# draft9.net
KiCad netlist of a schematic drawn in EAGLE
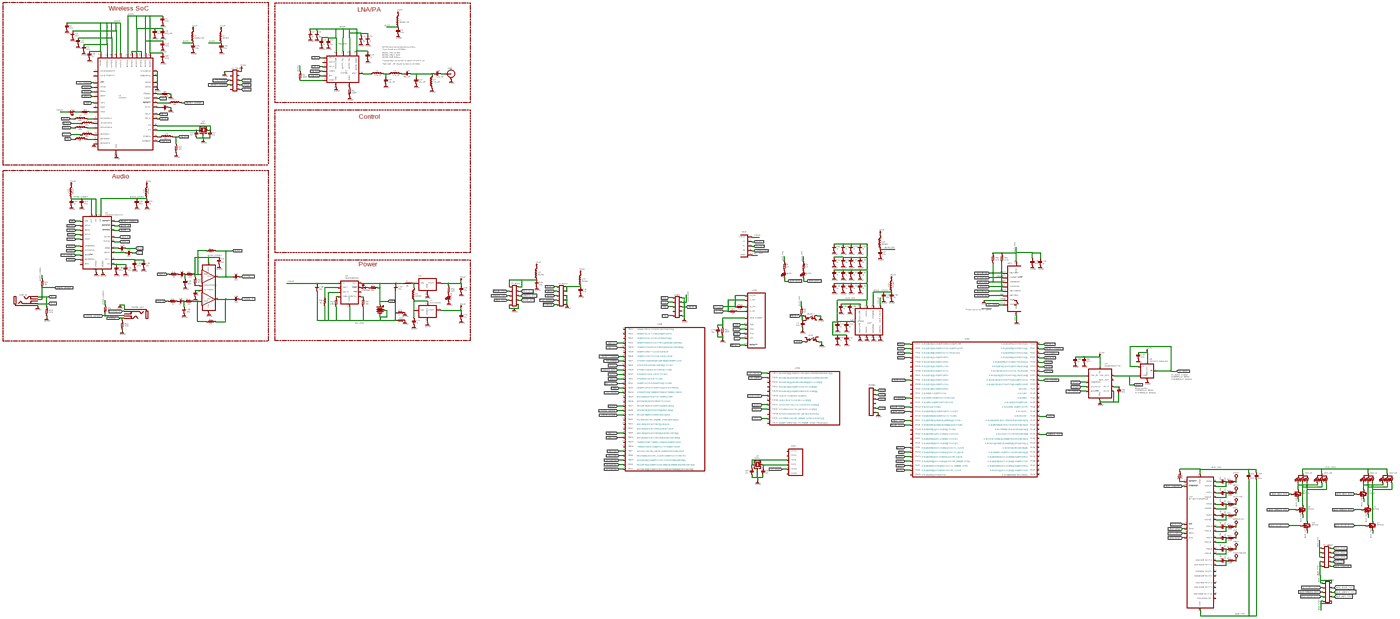
[diagram p0: schematic, sheet 1, overview]
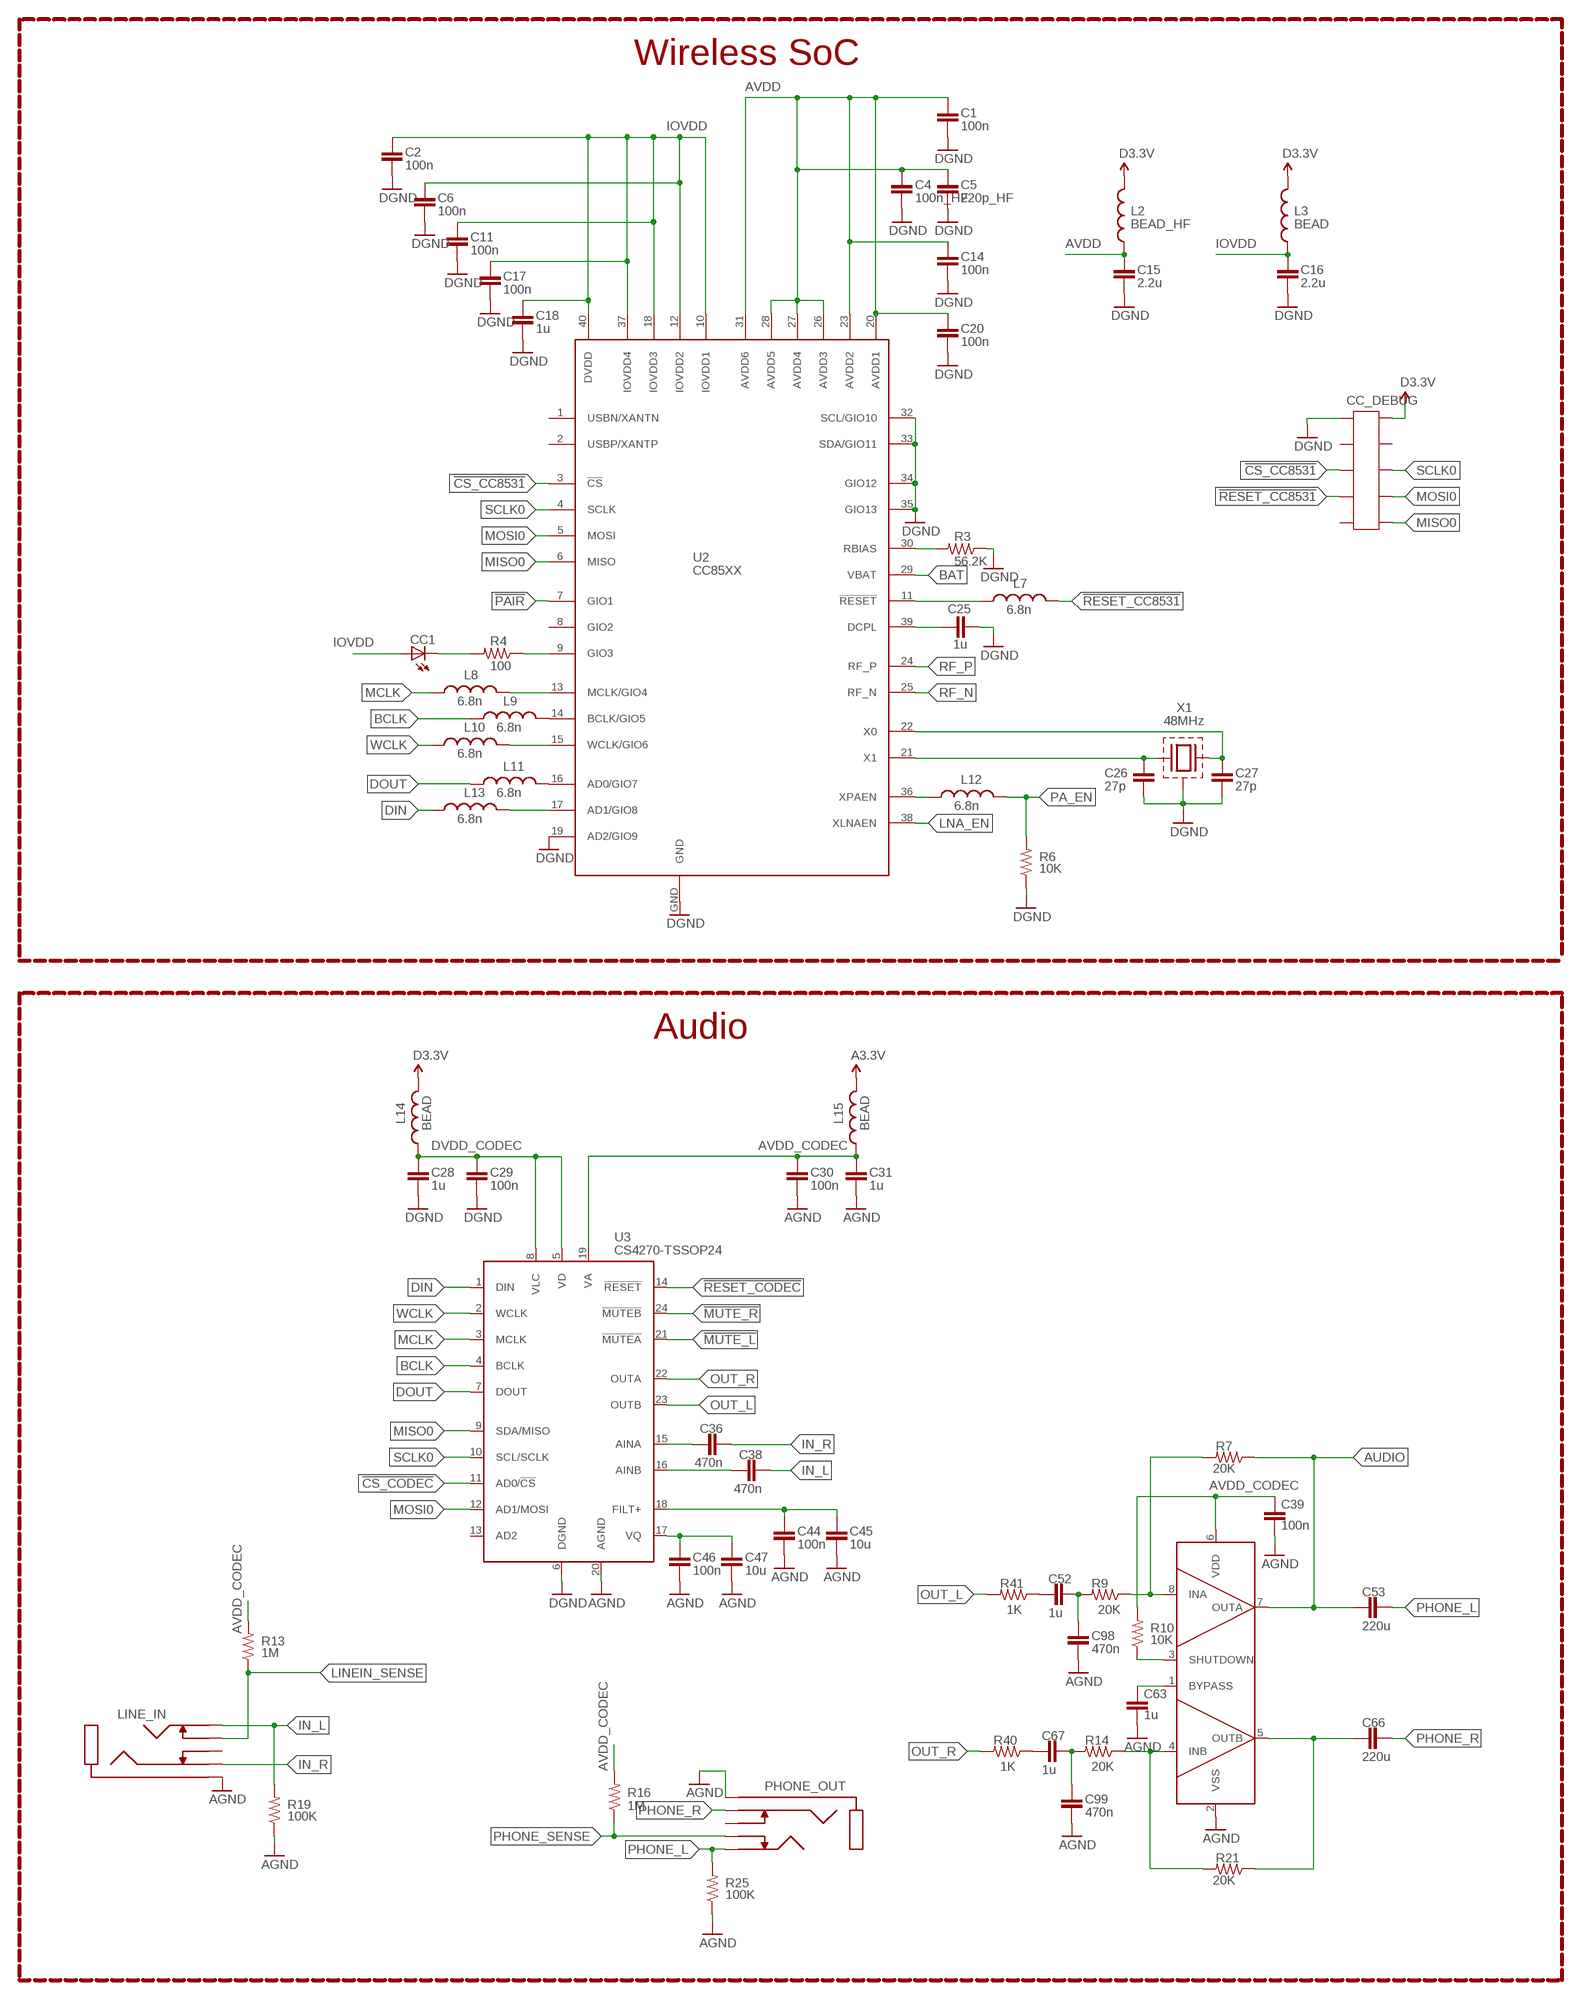
[diagram p1: schematic, sheet 1, part 1 of 4]
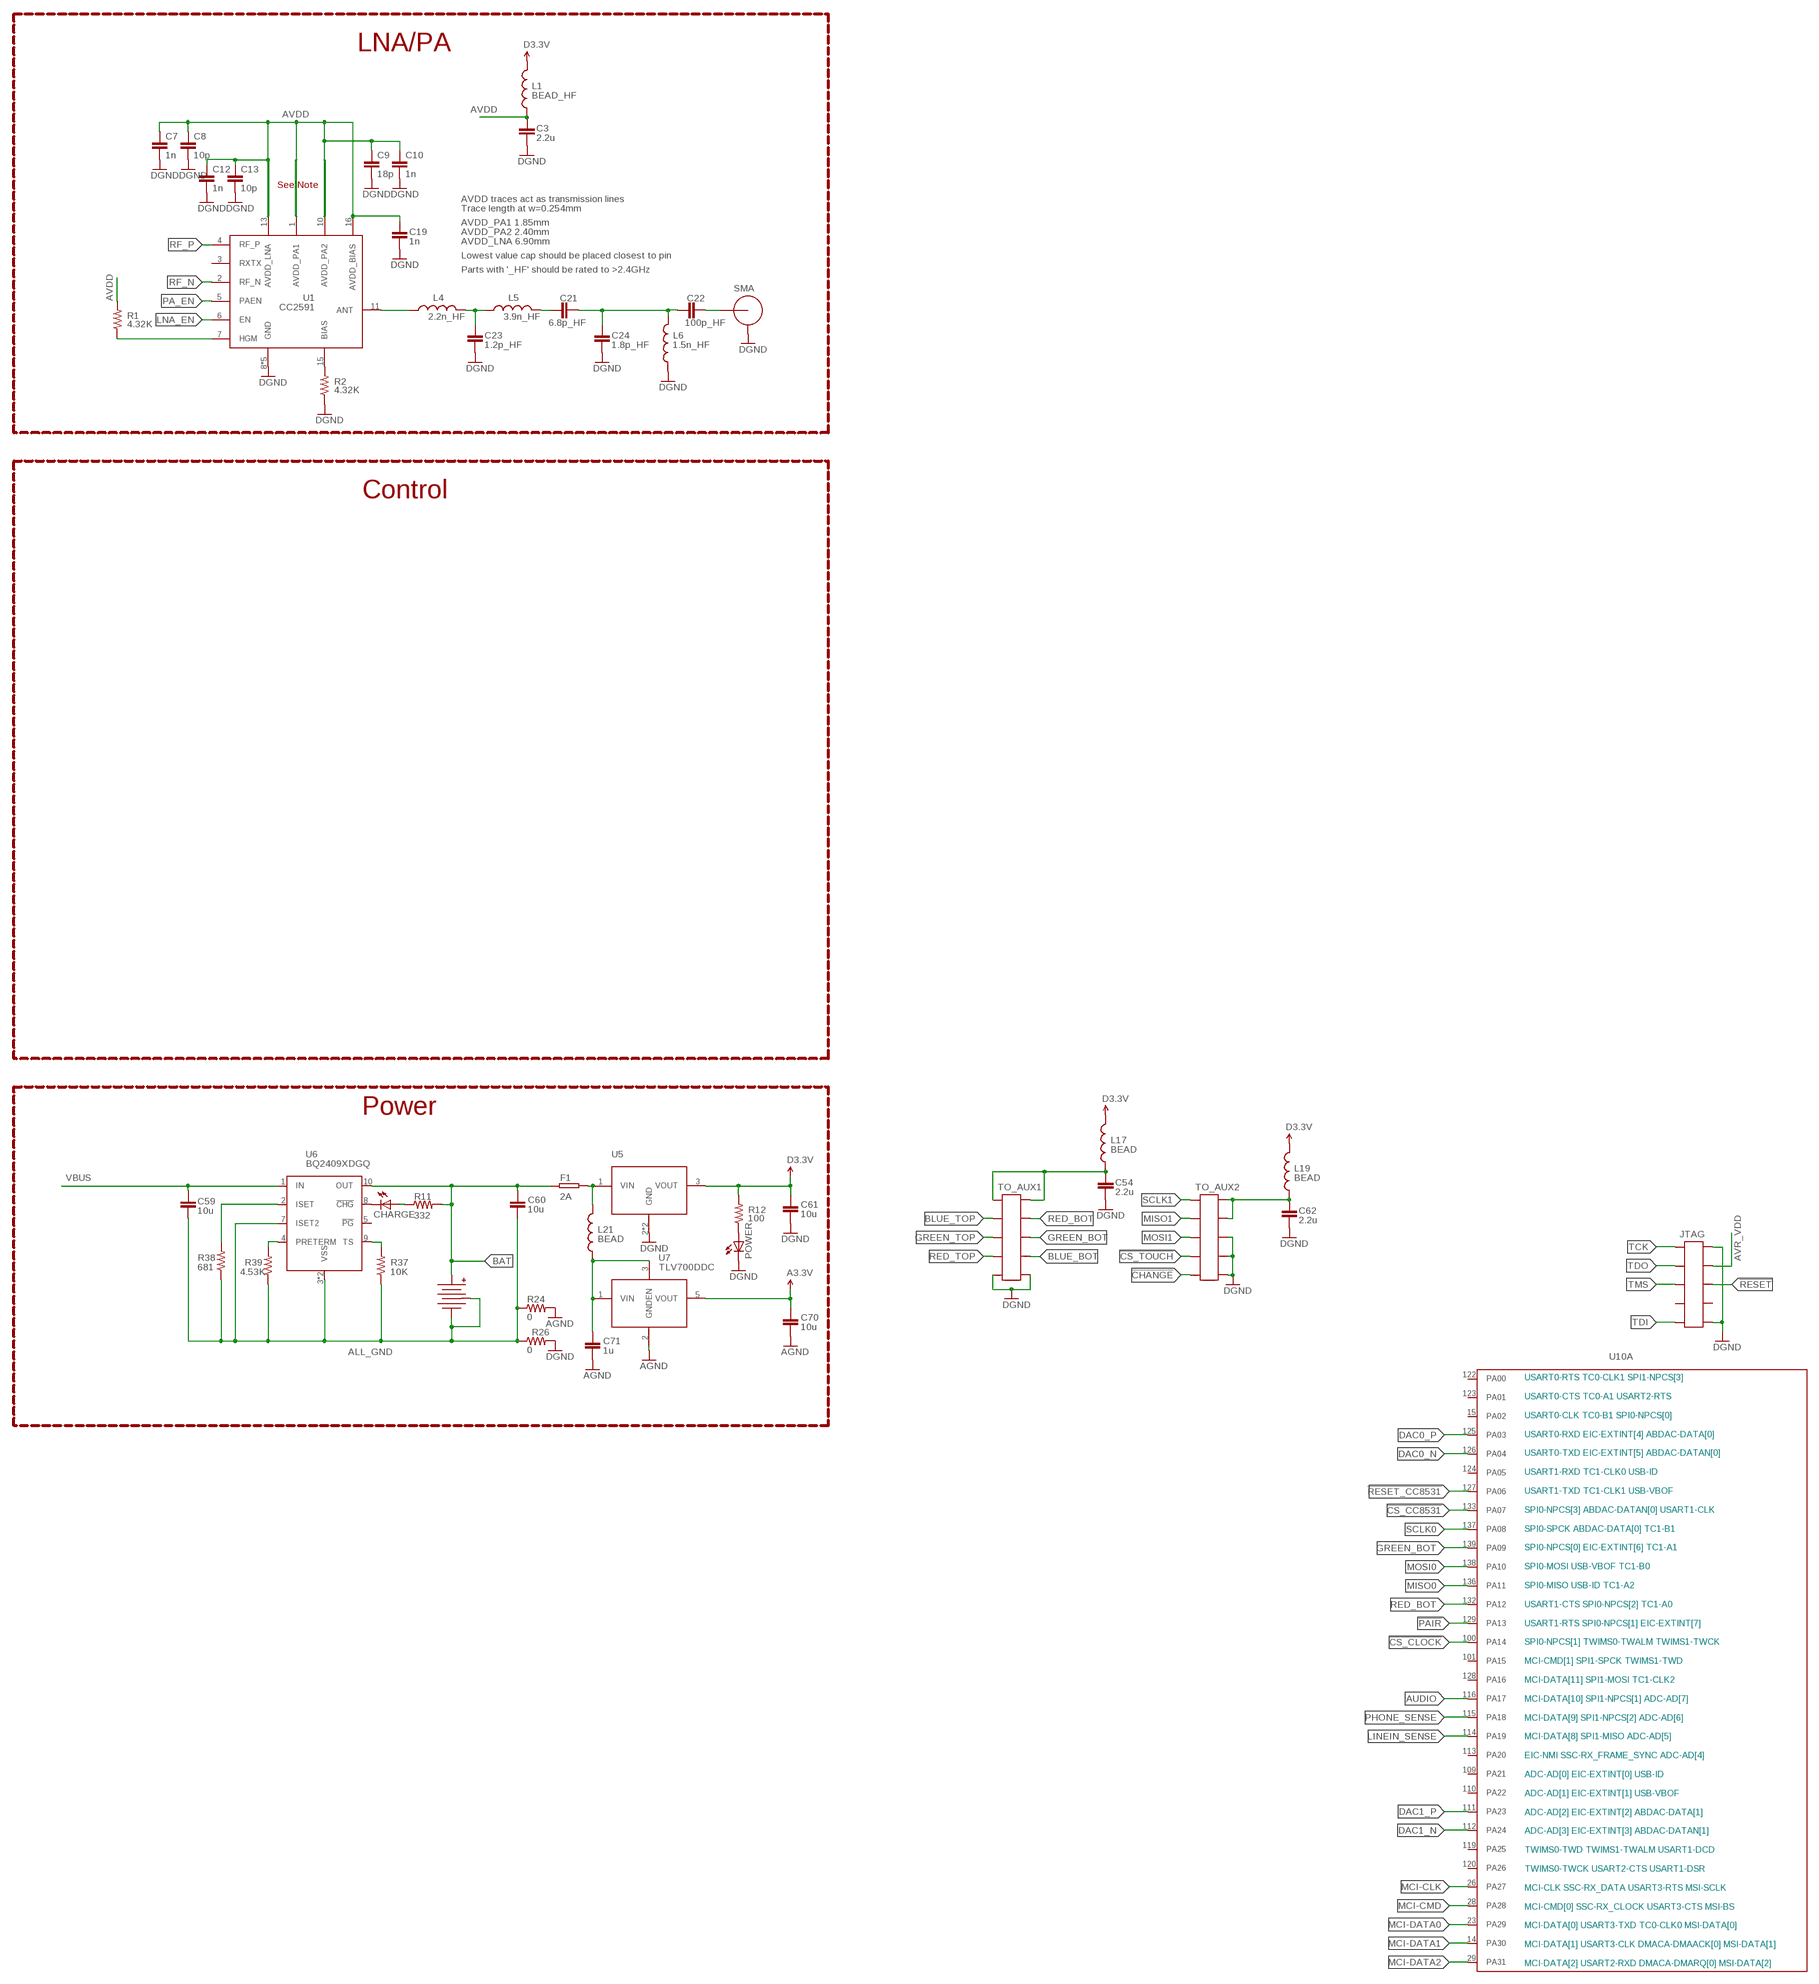
[diagram p2: schematic, sheet 1, part 2 of 4]
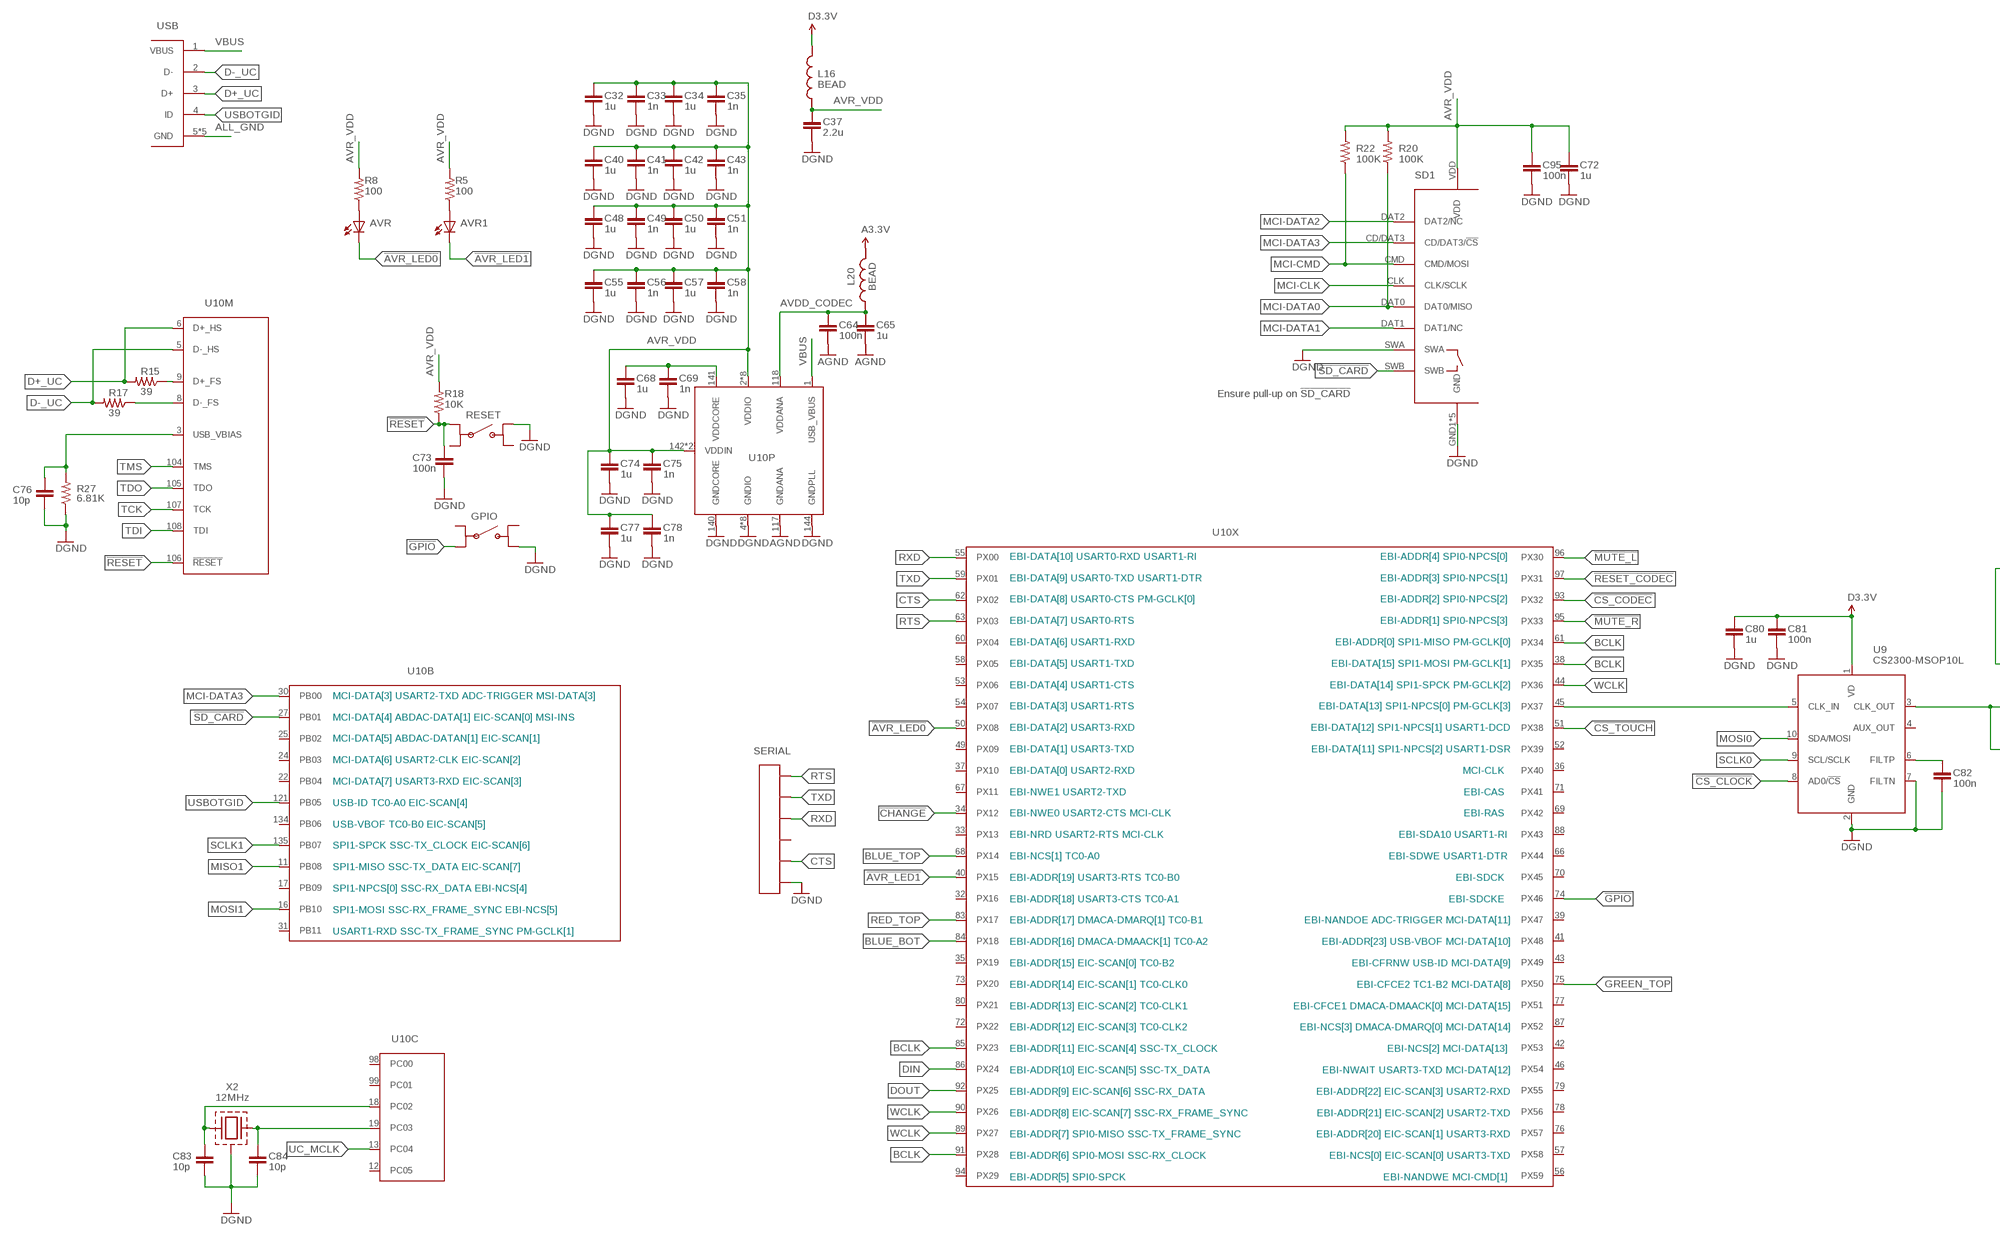
[diagram p3: schematic, sheet 1, part 3 of 4]
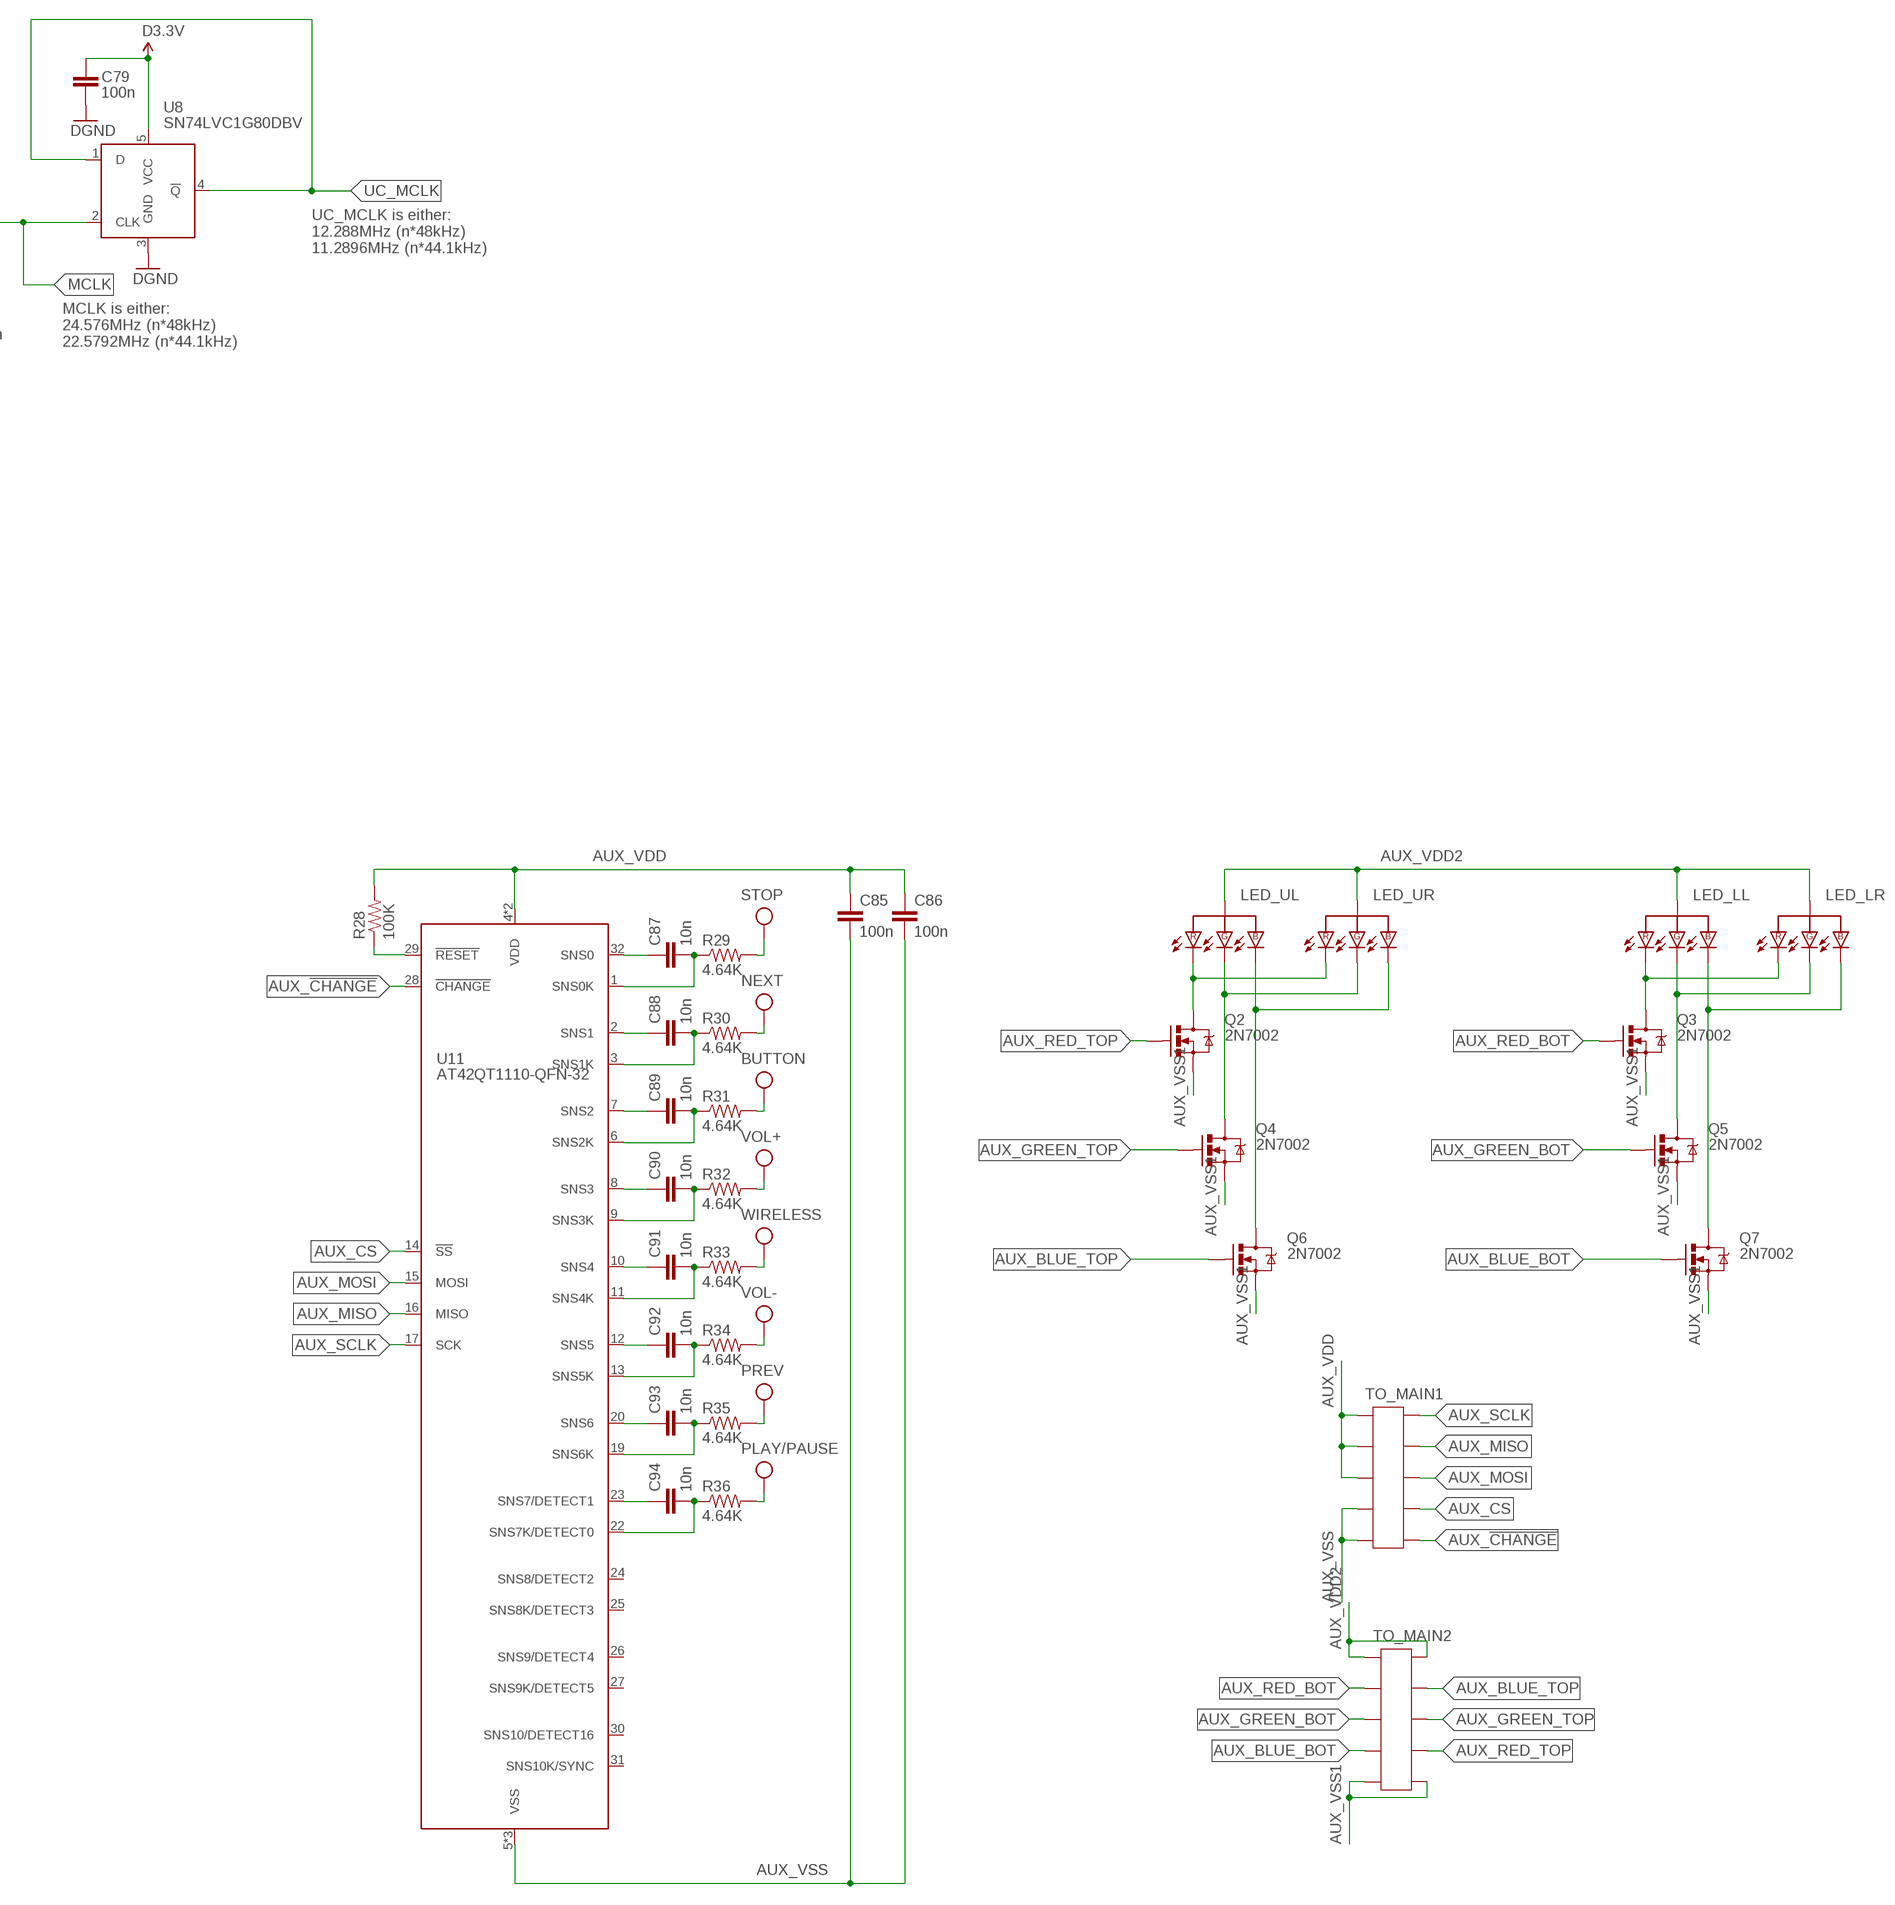
[diagram p4: schematic, sheet 1, part 4 of 4]

(export (version "E")
  (design (tool "Eeschema 10.0.6"))
  (components
    (comp (ref "AVR")
      (value "LED1206")
      (footprint "eagle-import:LED-1206")
      (libsource (lib "eagle-import") (part "LED1206"))
    )
    (comp (ref "AVR1")
      (value "LED1206")
      (footprint "eagle-import:LED-1206")
      (libsource (lib "eagle-import") (part "LED1206"))
    )
    (comp (ref "BATTERY")
      (value "BATTERY-LIPO-JST")
      (footprint "eagle-import:1775469-2")
      (libsource (lib "eagle-import") (part "BATTERY-LIPO-JST"))
    )
    (comp (ref "BUTTON")
      (value "TOUCH_PAD-CIRCLE-10MM")
      (footprint "eagle-import:TOUCH-CIRCLE-10MM")
      (libsource (lib "eagle-import") (part "TOUCH_PAD-CIRCLE-10MM"))
    )
    (comp (ref "C1")
      (value "100n")
      (footprint "eagle-import:C0603")
      (libsource (lib "eagle-import") (part "C-EUC0603"))
    )
    (comp (ref "C2")
      (value "100n")
      (footprint "eagle-import:C0603")
      (libsource (lib "eagle-import") (part "C-EUC0603"))
    )
    (comp (ref "C3")
      (value "2.2u")
      (footprint "eagle-import:C0603")
      (libsource (lib "eagle-import") (part "C-EUC0603"))
    )
    (comp (ref "C4")
      (value "100n_HF")
      (footprint "eagle-import:C0603")
      (libsource (lib "eagle-import") (part "C-EUC0603"))
    )
    (comp (ref "C5")
      (value "220p_HF")
      (footprint "eagle-import:C0603")
      (libsource (lib "eagle-import") (part "C-EUC0603"))
    )
    (comp (ref "C6")
      (value "100n")
      (footprint "eagle-import:C0603")
      (libsource (lib "eagle-import") (part "C-EUC0603"))
    )
    (comp (ref "C7")
      (value "1n")
      (footprint "eagle-import:C0603")
      (libsource (lib "eagle-import") (part "C-EUC0603"))
    )
    (comp (ref "C8")
      (value "10p")
      (footprint "eagle-import:C0603")
      (libsource (lib "eagle-import") (part "C-EUC0603"))
    )
    (comp (ref "C9")
      (value "18p")
      (footprint "eagle-import:C0603")
      (libsource (lib "eagle-import") (part "C-EUC0603"))
    )
    (comp (ref "C10")
      (value "1n")
      (footprint "eagle-import:C0603")
      (libsource (lib "eagle-import") (part "C-EUC0603"))
    )
    (comp (ref "C11")
      (value "100n")
      (footprint "eagle-import:C0603")
      (libsource (lib "eagle-import") (part "C-EUC0603"))
    )
    (comp (ref "C12")
      (value "1n")
      (footprint "eagle-import:C0603")
      (libsource (lib "eagle-import") (part "C-EUC0603"))
    )
    (comp (ref "C13")
      (value "10p")
      (footprint "eagle-import:C0603")
      (libsource (lib "eagle-import") (part "C-EUC0603"))
    )
    (comp (ref "C14")
      (value "100n")
      (footprint "eagle-import:C0603")
      (libsource (lib "eagle-import") (part "C-EUC0603"))
    )
    (comp (ref "C15")
      (value "2.2u")
      (footprint "eagle-import:C0603")
      (libsource (lib "eagle-import") (part "C-EUC0603"))
    )
    (comp (ref "C16")
      (value "2.2u")
      (footprint "eagle-import:C0603")
      (libsource (lib "eagle-import") (part "C-EUC0603"))
    )
    (comp (ref "C17")
      (value "100n")
      (footprint "eagle-import:C0603")
      (libsource (lib "eagle-import") (part "C-EUC0603"))
    )
    (comp (ref "C18")
      (value "1u")
      (footprint "eagle-import:C0603")
      (libsource (lib "eagle-import") (part "C-EUC0603"))
    )
    (comp (ref "C19")
      (value "1n")
      (footprint "eagle-import:C0603")
      (libsource (lib "eagle-import") (part "C-EUC0603"))
    )
    (comp (ref "C20")
      (value "100n")
      (footprint "eagle-import:C0603")
      (libsource (lib "eagle-import") (part "C-EUC0603"))
    )
    (comp (ref "C21")
      (value "6.8p_HF")
      (footprint "eagle-import:C0603")
      (libsource (lib "eagle-import") (part "C-EUC0603"))
    )
    (comp (ref "C22")
      (value "100p_HF")
      (footprint "eagle-import:C0603")
      (libsource (lib "eagle-import") (part "C-EUC0603"))
    )
    (comp (ref "C23")
      (value "1.2p_HF")
      (footprint "eagle-import:C0603")
      (libsource (lib "eagle-import") (part "C-EUC0603"))
    )
    (comp (ref "C24")
      (value "1.8p_HF")
      (footprint "eagle-import:C0603")
      (libsource (lib "eagle-import") (part "C-EUC0603"))
    )
    (comp (ref "C25")
      (value "1u")
      (footprint "eagle-import:C0603")
      (libsource (lib "eagle-import") (part "C-EUC0603"))
    )
    (comp (ref "C26")
      (value "27p")
      (footprint "eagle-import:C0603")
      (libsource (lib "eagle-import") (part "C-EUC0603"))
    )
    (comp (ref "C27")
      (value "27p")
      (footprint "eagle-import:C0603")
      (libsource (lib "eagle-import") (part "C-EUC0603"))
    )
    (comp (ref "C28")
      (value "1u")
      (footprint "eagle-import:C0603")
      (libsource (lib "eagle-import") (part "C-EUC0603"))
    )
    (comp (ref "C29")
      (value "100n")
      (footprint "eagle-import:C0603")
      (libsource (lib "eagle-import") (part "C-EUC0603"))
    )
    (comp (ref "C30")
      (value "100n")
      (footprint "eagle-import:C0603")
      (libsource (lib "eagle-import") (part "C-EUC0603"))
    )
    (comp (ref "C31")
      (value "1u")
      (footprint "eagle-import:C0603")
      (libsource (lib "eagle-import") (part "C-EUC0603"))
    )
    (comp (ref "C32")
      (value "1u")
      (footprint "eagle-import:C0603")
      (libsource (lib "eagle-import") (part "C-EUC0603"))
    )
    (comp (ref "C33")
      (value "1n")
      (footprint "eagle-import:C0603")
      (libsource (lib "eagle-import") (part "C-EUC0603"))
    )
    (comp (ref "C34")
      (value "1u")
      (footprint "eagle-import:C0603")
      (libsource (lib "eagle-import") (part "C-EUC0603"))
    )
    (comp (ref "C35")
      (value "1n")
      (footprint "eagle-import:C0603")
      (libsource (lib "eagle-import") (part "C-EUC0603"))
    )
    (comp (ref "C36")
      (value "470n")
      (footprint "eagle-import:C0603")
      (libsource (lib "eagle-import") (part "C-EUC0603"))
    )
    (comp (ref "C37")
      (value "2.2u")
      (footprint "eagle-import:C0603@1")
      (libsource (lib "eagle-import") (part "rcl_C-EUC0603"))
    )
    (comp (ref "C38")
      (value "470n")
      (footprint "eagle-import:C0603")
      (libsource (lib "eagle-import") (part "C-EUC0603"))
    )
    (comp (ref "C39")
      (value "100n")
      (footprint "eagle-import:C0603")
      (libsource (lib "eagle-import") (part "C-EUC0603"))
    )
    (comp (ref "C40")
      (value "1u")
      (footprint "eagle-import:C0603")
      (libsource (lib "eagle-import") (part "C-EUC0603"))
    )
    (comp (ref "C41")
      (value "1n")
      (footprint "eagle-import:C0603")
      (libsource (lib "eagle-import") (part "C-EUC0603"))
    )
    (comp (ref "C42")
      (value "1u")
      (footprint "eagle-import:C0603")
      (libsource (lib "eagle-import") (part "C-EUC0603"))
    )
    (comp (ref "C43")
      (value "1n")
      (footprint "eagle-import:C0603")
      (libsource (lib "eagle-import") (part "C-EUC0603"))
    )
    (comp (ref "C44")
      (value "100n")
      (footprint "eagle-import:C0603")
      (libsource (lib "eagle-import") (part "C-EUC0603"))
    )
    (comp (ref "C45")
      (value "10u")
      (footprint "eagle-import:C0603")
      (libsource (lib "eagle-import") (part "C-EUC0603"))
    )
    (comp (ref "C46")
      (value "100n")
      (footprint "eagle-import:C0603")
      (libsource (lib "eagle-import") (part "C-EUC0603"))
    )
    (comp (ref "C47")
      (value "10u")
      (footprint "eagle-import:C0603")
      (libsource (lib "eagle-import") (part "C-EUC0603"))
    )
    (comp (ref "C48")
      (value "1u")
      (footprint "eagle-import:C0603")
      (libsource (lib "eagle-import") (part "C-EUC0603"))
    )
    (comp (ref "C49")
      (value "1n")
      (footprint "eagle-import:C0603")
      (libsource (lib "eagle-import") (part "C-EUC0603"))
    )
    (comp (ref "C50")
      (value "1u")
      (footprint "eagle-import:C0603")
      (libsource (lib "eagle-import") (part "C-EUC0603"))
    )
    (comp (ref "C51")
      (value "1n")
      (footprint "eagle-import:C0603")
      (libsource (lib "eagle-import") (part "C-EUC0603"))
    )
    (comp (ref "C52")
      (value "1u")
      (footprint "eagle-import:C0603")
      (libsource (lib "eagle-import") (part "C-EUC0603"))
    )
    (comp (ref "C53")
      (value "220u")
      (footprint "eagle-import:C1210")
      (libsource (lib "eagle-import") (part "C-EUC1210"))
    )
    (comp (ref "C54")
      (value "2.2u")
      (footprint "eagle-import:C0603")
      (libsource (lib "eagle-import") (part "C-EUC0603"))
    )
    (comp (ref "C55")
      (value "1u")
      (footprint "eagle-import:C0603")
      (libsource (lib "eagle-import") (part "C-EUC0603"))
    )
    (comp (ref "C56")
      (value "1n")
      (footprint "eagle-import:C0603")
      (libsource (lib "eagle-import") (part "C-EUC0603"))
    )
    (comp (ref "C57")
      (value "1u")
      (footprint "eagle-import:C0603")
      (libsource (lib "eagle-import") (part "C-EUC0603"))
    )
    (comp (ref "C58")
      (value "1n")
      (footprint "eagle-import:C0603")
      (libsource (lib "eagle-import") (part "C-EUC0603"))
    )
    (comp (ref "C59")
      (value "10u")
      (footprint "eagle-import:C0603")
      (libsource (lib "eagle-import") (part "C-EUC0603"))
    )
    (comp (ref "C60")
      (value "10u")
      (footprint "eagle-import:C0603")
      (libsource (lib "eagle-import") (part "C-EUC0603"))
    )
    (comp (ref "C61")
      (value "10u")
      (footprint "eagle-import:C0603")
      (libsource (lib "eagle-import") (part "C-EUC0603"))
    )
    (comp (ref "C62")
      (value "2.2u")
      (footprint "eagle-import:C0603")
      (libsource (lib "eagle-import") (part "C-EUC0603"))
    )
    (comp (ref "C63")
      (value "1u")
      (footprint "eagle-import:C0603")
      (libsource (lib "eagle-import") (part "C-EUC0603"))
    )
    (comp (ref "C64")
      (value "100n")
      (footprint "eagle-import:C0603")
      (libsource (lib "eagle-import") (part "C-EUC0603"))
    )
    (comp (ref "C65")
      (value "1u")
      (footprint "eagle-import:C0603")
      (libsource (lib "eagle-import") (part "C-EUC0603"))
    )
    (comp (ref "C66")
      (value "220u")
      (footprint "eagle-import:C1210")
      (libsource (lib "eagle-import") (part "C-EUC1210"))
    )
    (comp (ref "C67")
      (value "1u")
      (footprint "eagle-import:C0603")
      (libsource (lib "eagle-import") (part "C-EUC0603"))
    )
    (comp (ref "C68")
      (value "1u")
      (footprint "eagle-import:C0603")
      (libsource (lib "eagle-import") (part "C-EUC0603"))
    )
    (comp (ref "C69")
      (value "1n")
      (footprint "eagle-import:C0603")
      (libsource (lib "eagle-import") (part "C-EUC0603"))
    )
    (comp (ref "C70")
      (value "10u")
      (footprint "eagle-import:C0603@1")
      (libsource (lib "eagle-import") (part "rcl_C-EUC0603"))
    )
    (comp (ref "C71")
      (value "1u")
      (footprint "eagle-import:C0603")
      (libsource (lib "eagle-import") (part "C-EUC0603"))
    )
    (comp (ref "C72")
      (value "1u")
      (footprint "eagle-import:C0603")
      (libsource (lib "eagle-import") (part "C-EUC0603"))
    )
    (comp (ref "C73")
      (value "100n")
      (footprint "eagle-import:C0603")
      (libsource (lib "eagle-import") (part "C-EUC0603"))
    )
    (comp (ref "C74")
      (value "1u")
      (footprint "eagle-import:C0603")
      (libsource (lib "eagle-import") (part "C-EUC0603"))
    )
    (comp (ref "C75")
      (value "1n")
      (footprint "eagle-import:C0603")
      (libsource (lib "eagle-import") (part "C-EUC0603"))
    )
    (comp (ref "C76")
      (value "10p")
      (footprint "eagle-import:C0603")
      (libsource (lib "eagle-import") (part "C-EUC0603"))
    )
    (comp (ref "C77")
      (value "1u")
      (footprint "eagle-import:C0603")
      (libsource (lib "eagle-import") (part "C-EUC0603"))
    )
    (comp (ref "C78")
      (value "1n")
      (footprint "eagle-import:C0603")
      (libsource (lib "eagle-import") (part "C-EUC0603"))
    )
    (comp (ref "C79")
      (value "100n")
      (footprint "eagle-import:C0603")
      (libsource (lib "eagle-import") (part "C-EUC0603"))
    )
    (comp (ref "C80")
      (value "1u")
      (footprint "eagle-import:C0603")
      (libsource (lib "eagle-import") (part "C-EUC0603"))
    )
    (comp (ref "C81")
      (value "100n")
      (footprint "eagle-import:C0603")
      (libsource (lib "eagle-import") (part "C-EUC0603"))
    )
    (comp (ref "C82")
      (value "100n")
      (footprint "eagle-import:C0603")
      (libsource (lib "eagle-import") (part "C-EUC0603"))
    )
    (comp (ref "C83")
      (value "10p")
      (footprint "eagle-import:C0603")
      (libsource (lib "eagle-import") (part "C-EUC0603"))
    )
    (comp (ref "C84")
      (value "10p")
      (footprint "eagle-import:C0603")
      (libsource (lib "eagle-import") (part "C-EUC0603"))
    )
    (comp (ref "C85")
      (value "100n")
      (footprint "eagle-import:C0603")
      (libsource (lib "eagle-import") (part "C-EUC0603"))
    )
    (comp (ref "C86")
      (value "100n")
      (footprint "eagle-import:C0603")
      (libsource (lib "eagle-import") (part "C-EUC0603"))
    )
    (comp (ref "C87")
      (value "10n")
      (footprint "eagle-import:C0603")
      (libsource (lib "eagle-import") (part "C-EUC0603"))
    )
    (comp (ref "C88")
      (value "10n")
      (footprint "eagle-import:C0603")
      (libsource (lib "eagle-import") (part "C-EUC0603"))
    )
    (comp (ref "C89")
      (value "10n")
      (footprint "eagle-import:C0603")
      (libsource (lib "eagle-import") (part "C-EUC0603"))
    )
    (comp (ref "C90")
      (value "10n")
      (footprint "eagle-import:C0603")
      (libsource (lib "eagle-import") (part "C-EUC0603"))
    )
    (comp (ref "C91")
      (value "10n")
      (footprint "eagle-import:C0603")
      (libsource (lib "eagle-import") (part "C-EUC0603"))
    )
    (comp (ref "C92")
      (value "10n")
      (footprint "eagle-import:C0603")
      (libsource (lib "eagle-import") (part "C-EUC0603"))
    )
    (comp (ref "C93")
      (value "10n")
      (footprint "eagle-import:C0603")
      (libsource (lib "eagle-import") (part "C-EUC0603"))
    )
    (comp (ref "C94")
      (value "10n")
      (footprint "eagle-import:C0603")
      (libsource (lib "eagle-import") (part "C-EUC0603"))
    )
    (comp (ref "C95")
      (value "100n")
      (footprint "eagle-import:C0603")
      (libsource (lib "eagle-import") (part "C-EUC0603"))
    )
    (comp (ref "C98")
      (value "470n")
      (footprint "eagle-import:C0603")
      (libsource (lib "eagle-import") (part "C-EUC0603"))
    )
    (comp (ref "C99")
      (value "470n")
      (footprint "eagle-import:C0603")
      (libsource (lib "eagle-import") (part "C-EUC0603"))
    )
    (comp (ref "CC1")
      (value "LED1206")
      (footprint "eagle-import:LED-1206")
      (libsource (lib "eagle-import") (part "LED1206"))
    )
    (comp (ref "CC_DEBUG")
      (value "HEADER-10P-SMD-MALE2")
      (footprint "eagle-import:HEADER-10P-1.27MM")
      (libsource (lib "eagle-import") (part "HEADER-10P-SMD-MALE2"))
    )
    (comp (ref "CHARGE")
      (value "LED1206")
      (footprint "eagle-import:LED-1206")
      (libsource (lib "eagle-import") (part "LED1206"))
    )
    (comp (ref "F1")
      (value "2A")
      (footprint "eagle-import:1210")
      (libsource (lib "eagle-import") (part "PTC_FUSE"))
    )
    (comp (ref "GPIO")
      (value "TACT_SWITCH-PTS-525")
      (footprint "eagle-import:PTS-525")
      (libsource (lib "eagle-import") (part "TACT_SWITCH-PTS-525"))
    )
    (comp (ref "JTAG")
      (value "HEADER-10P-SMD-MALE2")
      (footprint "eagle-import:HEADER-10P-1.27MM")
      (libsource (lib "eagle-import") (part "HEADER-10P-SMD-MALE2"))
    )
    (comp (ref "L1")
      (value "BEAD_HF")
      (footprint "eagle-import:0603")
      (libsource (lib "eagle-import") (part "INDUCTOR0603"))
    )
    (comp (ref "L2")
      (value "BEAD_HF")
      (footprint "eagle-import:0603")
      (libsource (lib "eagle-import") (part "INDUCTOR0603"))
    )
    (comp (ref "L3")
      (value "BEAD")
      (footprint "eagle-import:0603")
      (libsource (lib "eagle-import") (part "INDUCTOR0603"))
    )
    (comp (ref "L4")
      (value "2.2n_HF")
      (footprint "eagle-import:0603")
      (libsource (lib "eagle-import") (part "INDUCTOR0603"))
    )
    (comp (ref "L5")
      (value "3.9n_HF")
      (footprint "eagle-import:0603")
      (libsource (lib "eagle-import") (part "INDUCTOR0603"))
    )
    (comp (ref "L6")
      (value "1.5n_HF")
      (footprint "eagle-import:0603")
      (libsource (lib "eagle-import") (part "INDUCTOR0603"))
    )
    (comp (ref "L7")
      (value "6.8n")
      (footprint "eagle-import:0603")
      (libsource (lib "eagle-import") (part "INDUCTOR0603"))
    )
    (comp (ref "L8")
      (value "6.8n")
      (footprint "eagle-import:0603")
      (libsource (lib "eagle-import") (part "INDUCTOR0603"))
    )
    (comp (ref "L9")
      (value "6.8n")
      (footprint "eagle-import:0603")
      (libsource (lib "eagle-import") (part "INDUCTOR0603"))
    )
    (comp (ref "L10")
      (value "6.8n")
      (footprint "eagle-import:0603")
      (libsource (lib "eagle-import") (part "INDUCTOR0603"))
    )
    (comp (ref "L11")
      (value "6.8n")
      (footprint "eagle-import:0603")
      (libsource (lib "eagle-import") (part "INDUCTOR0603"))
    )
    (comp (ref "L12")
      (value "6.8n")
      (footprint "eagle-import:0603@1")
      (libsource (lib "eagle-import") (part "SparkFun-Passives_INDUCTOR0603"))
    )
    (comp (ref "L13")
      (value "6.8n")
      (footprint "eagle-import:0603")
      (libsource (lib "eagle-import") (part "INDUCTOR0603"))
    )
    (comp (ref "L14")
      (value "BEAD")
      (footprint "eagle-import:0603")
      (libsource (lib "eagle-import") (part "INDUCTOR0603"))
    )
    (comp (ref "L15")
      (value "BEAD")
      (footprint "eagle-import:0603@1")
      (libsource (lib "eagle-import") (part "SparkFun-Passives_INDUCTOR0603"))
    )
    (comp (ref "L16")
      (value "BEAD")
      (footprint "eagle-import:0603@1")
      (libsource (lib "eagle-import") (part "SparkFun-Passives_INDUCTOR0603"))
    )
    (comp (ref "L17")
      (value "BEAD")
      (footprint "eagle-import:0603")
      (libsource (lib "eagle-import") (part "INDUCTOR0603"))
    )
    (comp (ref "L19")
      (value "BEAD")
      (footprint "eagle-import:0603")
      (libsource (lib "eagle-import") (part "INDUCTOR0603"))
    )
    (comp (ref "L20")
      (value "BEAD")
      (footprint "eagle-import:0603")
      (libsource (lib "eagle-import") (part "INDUCTOR0603"))
    )
    (comp (ref "L21")
      (value "BEAD")
      (footprint "eagle-import:0603")
      (libsource (lib "eagle-import") (part "INDUCTOR0603"))
    )
    (comp (ref "LED_LL")
      (value "LED_RGB")
      (footprint "eagle-import:PLCC-4")
      (libsource (lib "eagle-import") (part "LED_RGB"))
    )
    (comp (ref "LED_LR")
      (value "LED_RGB")
      (footprint "eagle-import:PLCC-4")
      (libsource (lib "eagle-import") (part "LED_RGB"))
    )
    (comp (ref "LED_UL")
      (value "LED_RGB")
      (footprint "eagle-import:PLCC-4")
      (libsource (lib "eagle-import") (part "LED_RGB"))
    )
    (comp (ref "LED_UR")
      (value "LED_RGB")
      (footprint "eagle-import:PLCC-4")
      (libsource (lib "eagle-import") (part "LED_RGB"))
    )
    (comp (ref "LINE_IN")
      (value "PHONE_SW-STX-35332-5N")
      (footprint "eagle-import:STX-35332-5N")
      (libsource (lib "eagle-import") (part "PHONE_SW-STX-35332-5N"))
    )
    (comp (ref "NEXT")
      (value "TOUCH_PAD-CIRCLE-10MM")
      (footprint "eagle-import:TOUCH-CIRCLE-10MM")
      (libsource (lib "eagle-import") (part "TOUCH_PAD-CIRCLE-10MM"))
    )
    (comp (ref "PHONE_OUT")
      (value "PHONE_SW-STX-35332-5N")
      (footprint "eagle-import:STX-35332-5N")
      (libsource (lib "eagle-import") (part "PHONE_SW-STX-35332-5N"))
    )
    (comp (ref "PLAY/PAUSE")
      (value "TOUCH_PAD-CIRCLE-10MM")
      (footprint "eagle-import:TOUCH-CIRCLE-10MM")
      (libsource (lib "eagle-import") (part "TOUCH_PAD-CIRCLE-10MM"))
    )
    (comp (ref "POWER")
      (value "LED1206")
      (footprint "eagle-import:LED-1206")
      (libsource (lib "eagle-import") (part "LED1206"))
    )
    (comp (ref "PREV")
      (value "TOUCH_PAD-CIRCLE-10MM")
      (footprint "eagle-import:TOUCH-CIRCLE-10MM")
      (libsource (lib "eagle-import") (part "TOUCH_PAD-CIRCLE-10MM"))
    )
    (comp (ref "Q2")
      (value "2N7002")
      (footprint "eagle-import:SOT23-3")
      (libsource (lib "eagle-import") (part "MOSFET-NCHANNELSMD"))
    )
    (comp (ref "Q3")
      (value "2N7002")
      (footprint "eagle-import:SOT23-3")
      (libsource (lib "eagle-import") (part "MOSFET-NCHANNELSMD"))
    )
    (comp (ref "Q4")
      (value "2N7002")
      (footprint "eagle-import:SOT23-3")
      (libsource (lib "eagle-import") (part "MOSFET-NCHANNELSMD"))
    )
    (comp (ref "Q5")
      (value "2N7002")
      (footprint "eagle-import:SOT23-3")
      (libsource (lib "eagle-import") (part "MOSFET-NCHANNELSMD"))
    )
    (comp (ref "Q6")
      (value "2N7002")
      (footprint "eagle-import:SOT23-3")
      (libsource (lib "eagle-import") (part "MOSFET-NCHANNELSMD"))
    )
    (comp (ref "Q7")
      (value "2N7002")
      (footprint "eagle-import:SOT23-3")
      (libsource (lib "eagle-import") (part "MOSFET-NCHANNELSMD"))
    )
    (comp (ref "R1")
      (value "4.32K")
      (footprint "eagle-import:R0603")
      (libsource (lib "eagle-import") (part "R-US_R0603"))
    )
    (comp (ref "R2")
      (value "4.32K")
      (footprint "eagle-import:R0603")
      (libsource (lib "eagle-import") (part "R-US_R0603"))
    )
    (comp (ref "R3")
      (value "56.2K")
      (footprint "eagle-import:R0603")
      (libsource (lib "eagle-import") (part "R-US_R0603"))
    )
    (comp (ref "R4")
      (value "100")
      (footprint "eagle-import:R0603")
      (libsource (lib "eagle-import") (part "R-US_R0603"))
    )
    (comp (ref "R5")
      (value "100")
      (footprint "eagle-import:R0603")
      (libsource (lib "eagle-import") (part "R-US_R0603"))
    )
    (comp (ref "R6")
      (value "10K")
      (footprint "eagle-import:R0603")
      (libsource (lib "eagle-import") (part "R-US_R0603"))
    )
    (comp (ref "R7")
      (value "20K")
      (footprint "eagle-import:R0603")
      (libsource (lib "eagle-import") (part "R-US_R0603"))
    )
    (comp (ref "R8")
      (value "100")
      (footprint "eagle-import:R0603")
      (libsource (lib "eagle-import") (part "R-US_R0603"))
    )
    (comp (ref "R9")
      (value "20K")
      (footprint "eagle-import:R0603")
      (libsource (lib "eagle-import") (part "R-US_R0603"))
    )
    (comp (ref "R10")
      (value "10K")
      (footprint "eagle-import:R0603@1")
      (libsource (lib "eagle-import") (part "rcl_R-US_R0603"))
    )
    (comp (ref "R11")
      (value "332")
      (footprint "eagle-import:R0603")
      (libsource (lib "eagle-import") (part "R-US_R0603"))
    )
    (comp (ref "R12")
      (value "100")
      (footprint "eagle-import:R0603")
      (libsource (lib "eagle-import") (part "R-US_R0603"))
    )
    (comp (ref "R13")
      (value "1M")
      (footprint "eagle-import:R0603")
      (libsource (lib "eagle-import") (part "R-US_R0603"))
    )
    (comp (ref "R14")
      (value "20K")
      (footprint "eagle-import:R0603")
      (libsource (lib "eagle-import") (part "R-US_R0603"))
    )
    (comp (ref "R15")
      (value "39")
      (footprint "eagle-import:R0603")
      (libsource (lib "eagle-import") (part "R-US_R0603"))
    )
    (comp (ref "R16")
      (value "1M")
      (footprint "eagle-import:R0603")
      (libsource (lib "eagle-import") (part "R-US_R0603"))
    )
    (comp (ref "R17")
      (value "39")
      (footprint "eagle-import:R0603")
      (libsource (lib "eagle-import") (part "R-US_R0603"))
    )
    (comp (ref "R18")
      (value "10K")
      (footprint "eagle-import:R0603")
      (libsource (lib "eagle-import") (part "R-US_R0603"))
    )
    (comp (ref "R19")
      (value "100K")
      (footprint "eagle-import:R0603")
      (libsource (lib "eagle-import") (part "R-US_R0603"))
    )
    (comp (ref "R20")
      (value "100K")
      (footprint "eagle-import:R0603")
      (libsource (lib "eagle-import") (part "R-US_R0603"))
    )
    (comp (ref "R21")
      (value "20K")
      (footprint "eagle-import:R0603")
      (libsource (lib "eagle-import") (part "R-US_R0603"))
    )
    (comp (ref "R22")
      (value "100K")
      (footprint "eagle-import:R0603")
      (libsource (lib "eagle-import") (part "R-US_R0603"))
    )
    (comp (ref "R24")
      (value "0")
      (footprint "eagle-import:R0603")
      (libsource (lib "eagle-import") (part "R-US_R0603"))
    )
    (comp (ref "R25")
      (value "100K")
      (footprint "eagle-import:R0603")
      (libsource (lib "eagle-import") (part "R-US_R0603"))
    )
    (comp (ref "R26")
      (value "0")
      (footprint "eagle-import:R0603")
      (libsource (lib "eagle-import") (part "R-US_R0603"))
    )
    (comp (ref "R27")
      (value "6.81K")
      (footprint "eagle-import:R0603")
      (libsource (lib "eagle-import") (part "R-US_R0603"))
    )
    (comp (ref "R28")
      (value "100K")
      (footprint "eagle-import:R0603")
      (libsource (lib "eagle-import") (part "R-US_R0603"))
    )
    (comp (ref "R29")
      (value "4.64K")
      (footprint "eagle-import:R0603")
      (libsource (lib "eagle-import") (part "R-US_R0603"))
    )
    (comp (ref "R30")
      (value "4.64K")
      (footprint "eagle-import:R0603")
      (libsource (lib "eagle-import") (part "R-US_R0603"))
    )
    (comp (ref "R31")
      (value "4.64K")
      (footprint "eagle-import:R0603")
      (libsource (lib "eagle-import") (part "R-US_R0603"))
    )
    (comp (ref "R32")
      (value "4.64K")
      (footprint "eagle-import:R0603")
      (libsource (lib "eagle-import") (part "R-US_R0603"))
    )
    (comp (ref "R33")
      (value "4.64K")
      (footprint "eagle-import:R0603")
      (libsource (lib "eagle-import") (part "R-US_R0603"))
    )
    (comp (ref "R34")
      (value "4.64K")
      (footprint "eagle-import:R0603")
      (libsource (lib "eagle-import") (part "R-US_R0603"))
    )
    (comp (ref "R35")
      (value "4.64K")
      (footprint "eagle-import:R0603")
      (libsource (lib "eagle-import") (part "R-US_R0603"))
    )
    (comp (ref "R36")
      (value "4.64K")
      (footprint "eagle-import:R0603")
      (libsource (lib "eagle-import") (part "R-US_R0603"))
    )
    (comp (ref "R37")
      (value "10K")
      (footprint "eagle-import:R0603")
      (libsource (lib "eagle-import") (part "R-US_R0603"))
    )
    (comp (ref "R38")
      (value "681")
      (footprint "eagle-import:R0603")
      (libsource (lib "eagle-import") (part "R-US_R0603"))
    )
    (comp (ref "R39")
      (value "4.53K")
      (footprint "eagle-import:R0603")
      (libsource (lib "eagle-import") (part "R-US_R0603"))
    )
    (comp (ref "R40")
      (value "1K")
      (footprint "eagle-import:R0603")
      (libsource (lib "eagle-import") (part "R-US_R0603"))
    )
    (comp (ref "R41")
      (value "1K")
      (footprint "eagle-import:R0603")
      (libsource (lib "eagle-import") (part "R-US_R0603"))
    )
    (comp (ref "RESET")
      (value "TACT_SWITCH-PTS-525")
      (footprint "eagle-import:PTS-525")
      (libsource (lib "eagle-import") (part "TACT_SWITCH-PTS-525"))
    )
    (comp (ref "SD1")
      (value "MICROSD104031-0811")
      (footprint "eagle-import:MOLEX_104031-0811")
      (libsource (lib "eagle-import") (part "MICROSD104031-0811"))
    )
    (comp (ref "SERIAL")
      (value "HEADER-6X1-961106-5500")
      (footprint "eagle-import:HEADER-3M-961-6P-2.54MM")
      (libsource (lib "eagle-import") (part "HEADER-6X1-961106-5500"))
    )
    (comp (ref "SMA")
      (value "SMA-REVSMA-0.62")
      (footprint "eagle-import:CONREVSMA003.062")
      (libsource (lib "eagle-import") (part "SMA-REVSMA-0.62"))
    )
    (comp (ref "STOP")
      (value "TOUCH_PAD-CIRCLE-10MM")
      (footprint "eagle-import:TOUCH-CIRCLE-10MM")
      (libsource (lib "eagle-import") (part "TOUCH_PAD-CIRCLE-10MM"))
    )
    (comp (ref "TO_AUX1")
      (value "HEADER-10P-SMD-2MM-FEMALE")
      (footprint "eagle-import:M22-63405")
      (libsource (lib "eagle-import") (part "HEADER-10P-SMD-2MM-FEMALE"))
    )
    (comp (ref "TO_AUX2")
      (value "HEADER-10P-SMD-2MM-FEMALE")
      (footprint "eagle-import:M22-63405")
      (libsource (lib "eagle-import") (part "HEADER-10P-SMD-2MM-FEMALE"))
    )
    (comp (ref "TO_MAIN1")
      (value "HEADER-10P-SMD-2MM-MALE")
      (footprint "eagle-import:M22-53205")
      (libsource (lib "eagle-import") (part "HEADER-10P-SMD-2MM-MALE"))
    )
    (comp (ref "TO_MAIN2")
      (value "HEADER-10P-SMD-2MM-MALE")
      (footprint "eagle-import:M22-53205")
      (libsource (lib "eagle-import") (part "HEADER-10P-SMD-2MM-MALE"))
    )
    (comp (ref "U1")
      (value "CC2591")
      (footprint "eagle-import:S-PVQFN-N16")
      (libsource (lib "eagle-import") (part "CC2591"))
    )
    (comp (ref "U2")
      (value "CC85XX")
      (footprint "eagle-import:S-PVQFN-N40")
      (libsource (lib "eagle-import") (part "CC85XX"))
    )
    (comp (ref "U3")
      (value "CS4270-TSSOP24")
      (footprint "eagle-import:TSSOP-24L")
      (libsource (lib "eagle-import") (part "CS4270-TSSOP24"))
    )
    (comp (ref "U4")
      (value "LM4881")
      (footprint "eagle-import:SO08")
      (libsource (lib "eagle-import") (part "LM4881"))
    )
    (comp (ref "U5")
      (value "MCP1826-SOT223")
      (footprint "eagle-import:SOT-223")
      (libsource (lib "eagle-import") (part "MCP1826-SOT223"))
    )
    (comp (ref "U6")
      (value "BQ2409XDGQ")
      (footprint "eagle-import:S-PDSO-G10")
      (libsource (lib "eagle-import") (part "BQ2409XDGQ"))
    )
    (comp (ref "U7")
      (value "TLV700DDC")
      (footprint "eagle-import:SOT-23-5")
      (libsource (lib "eagle-import") (part "TLV700DDC"))
    )
    (comp (ref "U8")
      (value "SN74LVC1G80DBV")
      (footprint "eagle-import:SOT-23-5")
      (libsource (lib "eagle-import") (part "SN74LVC1G80DBV"))
    )
    (comp (ref "U9")
      (value "CS2300-MSOP10L")
      (footprint "eagle-import:MSOP-10L")
      (libsource (lib "eagle-import") (part "CS2300-MSOP10L"))
    )
    (comp (ref "U10")
      (value "AT32UC3A3-LQFP-144")
      (footprint "eagle-import:LQFP-144")
      (libsource (lib "eagle-import") (part "AT32UC3A3-LQFP-144"))
    )
    (comp (ref "U11")
      (value "AT42QT1110-QFN-32")
      (footprint "eagle-import:QFN-32")
      (libsource (lib "eagle-import") (part "AT42QT1110-QFN-32"))
    )
    (comp (ref "USB")
      (value "USB_MICRO_AB")
      (footprint "eagle-import:USB_MICRO_AB")
      (libsource (lib "eagle-import") (part "USB_MICRO_AB"))
    )
    (comp (ref "VOL+")
      (value "TOUCH_PAD-CIRCLE-10MM")
      (footprint "eagle-import:TOUCH-CIRCLE-10MM")
      (libsource (lib "eagle-import") (part "TOUCH_PAD-CIRCLE-10MM"))
    )
    (comp (ref "VOL-")
      (value "TOUCH_PAD-CIRCLE-10MM")
      (footprint "eagle-import:TOUCH-CIRCLE-10MM")
      (libsource (lib "eagle-import") (part "TOUCH_PAD-CIRCLE-10MM"))
    )
    (comp (ref "WIRELESS")
      (value "TOUCH_PAD-CIRCLE-10MM")
      (footprint "eagle-import:TOUCH-CIRCLE-10MM")
      (libsource (lib "eagle-import") (part "TOUCH_PAD-CIRCLE-10MM"))
    )
    (comp (ref "X1")
      (value "48MHz")
      (footprint "eagle-import:ABM3C")
      (libsource (lib "eagle-import") (part "XTAL-ABRACONABM3C"))
    )
    (comp (ref "X2")
      (value "12MHz")
      (footprint "eagle-import:ABM8G")
      (libsource (lib "eagle-import") (part "XTAL-ABRACONABM8G"))
    )
  )
  (nets
    (net (code "1") (name "/ALL_GND") (class "Default")
      (node (ref "BATTERY") (pin "-") (pinfunction "N_-") (pintype "passive"))
      (node (ref "BATTERY") (pin "X1") (pinfunction "CASE_X1") (pintype "passive"))
      (node (ref "BATTERY") (pin "X2") (pinfunction "CASE_X2") (pintype "passive"))
      (node (ref "C59") (pin "2") (pinfunction "2_2") (pintype "passive"))
      (node (ref "C60") (pin "2") (pinfunction "2_2") (pintype "passive"))
      (node (ref "R24") (pin "1") (pinfunction "1_1") (pintype "passive"))
      (node (ref "R26") (pin "1") (pinfunction "1_1") (pintype "passive"))
      (node (ref "R37") (pin "1") (pinfunction "1_1") (pintype "passive"))
      (node (ref "R38") (pin "1") (pinfunction "1_1") (pintype "passive"))
      (node (ref "R39") (pin "1") (pinfunction "1_1") (pintype "passive"))
      (node (ref "U6") (pin "3") (pinfunction "VSS_3") (pintype "bidirectional"))
      (node (ref "U6") (pin "7") (pinfunction "ISET2_7") (pintype "bidirectional"))
      (node (ref "U6") (pin "GND") (pinfunction "VSS_GND") (pintype "bidirectional"))
      (node (ref "USB") (pin "5") (pinfunction "GND_5") (pintype "bidirectional"))
      (node (ref "USB") (pin "GND1") (pinfunction "GND_GND1") (pintype "bidirectional"))
      (node (ref "USB") (pin "GND2") (pinfunction "GND_GND2") (pintype "bidirectional"))
      (node (ref "USB") (pin "GND3") (pinfunction "GND_GND3") (pintype "bidirectional"))
      (node (ref "USB") (pin "GND4") (pinfunction "GND_GND4") (pintype "bidirectional"))
    )
    (net (code "2") (name "/AUX_VDD") (class "Default")
      (node (ref "C85") (pin "1") (pinfunction "1_1") (pintype "passive"))
      (node (ref "C86") (pin "1") (pinfunction "1_1") (pintype "passive"))
      (node (ref "R28") (pin "2") (pinfunction "2_2") (pintype "passive"))
      (node (ref "TO_MAIN1") (pin "1") (pinfunction "1_1") (pintype "bidirectional"))
      (node (ref "TO_MAIN1") (pin "3") (pinfunction "3_3") (pintype "bidirectional"))
      (node (ref "TO_MAIN1") (pin "5") (pinfunction "5_5") (pintype "bidirectional"))
      (node (ref "U11") (pin "18") (pinfunction "VDD_18") (pintype "bidirectional"))
      (node (ref "U11") (pin "4") (pinfunction "VDD_4") (pintype "bidirectional"))
    )
    (net (code "3") (name "/AUX_VDD2") (class "Default")
      (node (ref "LED_LL") (pin "2") (pinfunction "A_2") (pintype "passive"))
      (node (ref "LED_LL") (pin "2-2") (pinfunction "A_2-2") (pintype "passive"))
      (node (ref "LED_LR") (pin "2") (pinfunction "A_2") (pintype "passive"))
      (node (ref "LED_LR") (pin "2-2") (pinfunction "A_2-2") (pintype "passive"))
      (node (ref "LED_UL") (pin "2") (pinfunction "A_2") (pintype "passive"))
      (node (ref "LED_UL") (pin "2-2") (pinfunction "A_2-2") (pintype "passive"))
      (node (ref "LED_UR") (pin "2") (pinfunction "A_2") (pintype "passive"))
      (node (ref "LED_UR") (pin "2-2") (pinfunction "A_2-2") (pintype "passive"))
      (node (ref "TO_MAIN2") (pin "1") (pinfunction "1_1") (pintype "bidirectional"))
      (node (ref "TO_MAIN2") (pin "2") (pinfunction "2_2") (pintype "bidirectional"))
    )
    (net (code "4") (name "/AUX_VSS") (class "Default")
      (node (ref "C85") (pin "2") (pinfunction "2_2") (pintype "passive"))
      (node (ref "C86") (pin "2") (pinfunction "2_2") (pintype "passive"))
      (node (ref "TO_MAIN1") (pin "7") (pinfunction "7_7") (pintype "bidirectional"))
      (node (ref "TO_MAIN1") (pin "9") (pinfunction "9_9") (pintype "bidirectional"))
      (node (ref "U11") (pin "21") (pinfunction "VSS_21") (pintype "bidirectional"))
      (node (ref "U11") (pin "5") (pinfunction "VSS_5") (pintype "bidirectional"))
      (node (ref "U11") (pin "GND") (pinfunction "VSS_GND") (pintype "bidirectional"))
    )
    (net (code "5") (name "/AUX_VSS1") (class "Default")
      (node (ref "Q2") (pin "2") (pinfunction "S_2") (pintype "passive"))
      (node (ref "Q3") (pin "2") (pinfunction "S_2") (pintype "passive"))
      (node (ref "Q4") (pin "2") (pinfunction "S_2") (pintype "passive"))
      (node (ref "Q5") (pin "2") (pinfunction "S_2") (pintype "passive"))
      (node (ref "Q6") (pin "2") (pinfunction "S_2") (pintype "passive"))
      (node (ref "Q7") (pin "2") (pinfunction "S_2") (pintype "passive"))
      (node (ref "TO_MAIN2") (pin "10") (pinfunction "10_10") (pintype "bidirectional"))
      (node (ref "TO_MAIN2") (pin "9") (pinfunction "9_9") (pintype "bidirectional"))
    )
    (net (code "6") (name "/AUX_~{CHANGE}") (class "Default")
      (node (ref "TO_MAIN1") (pin "10") (pinfunction "10_10") (pintype "bidirectional"))
      (node (ref "U11") (pin "28") (pinfunction "~{CHANGE}_28") (pintype "bidirectional"))
    )
    (net (code "7") (name "/AVDD") (class "Default")
      (node (ref "C1") (pin "1") (pinfunction "1_1") (pintype "passive"))
      (node (ref "C10") (pin "1") (pinfunction "1_1") (pintype "passive"))
      (node (ref "C12") (pin "1") (pinfunction "1_1") (pintype "passive"))
      (node (ref "C13") (pin "1") (pinfunction "1_1") (pintype "passive"))
      (node (ref "C14") (pin "1") (pinfunction "1_1") (pintype "passive"))
      (node (ref "C15") (pin "1") (pinfunction "1_1") (pintype "passive"))
      (node (ref "C19") (pin "1") (pinfunction "1_1") (pintype "passive"))
      (node (ref "C20") (pin "1") (pinfunction "1_1") (pintype "passive"))
      (node (ref "C3") (pin "1") (pinfunction "1_1") (pintype "passive"))
      (node (ref "C4") (pin "1") (pinfunction "1_1") (pintype "passive"))
      (node (ref "C5") (pin "1") (pinfunction "1_1") (pintype "passive"))
      (node (ref "C7") (pin "1") (pinfunction "1_1") (pintype "passive"))
      (node (ref "C8") (pin "1") (pinfunction "1_1") (pintype "passive"))
      (node (ref "C9") (pin "1") (pinfunction "1_1") (pintype "passive"))
      (node (ref "L1") (pin "1") (pinfunction "1_1") (pintype "passive"))
      (node (ref "L2") (pin "1") (pinfunction "1_1") (pintype "passive"))
      (node (ref "R1") (pin "2") (pinfunction "2_2") (pintype "passive"))
      (node (ref "U1") (pin "1") (pinfunction "AVDD_PA1_1") (pintype "bidirectional"))
      (node (ref "U1") (pin "10") (pinfunction "AVDD_PA2_10") (pintype "bidirectional"))
      (node (ref "U1") (pin "13") (pinfunction "AVDD_LNA_13") (pintype "bidirectional"))
      (node (ref "U1") (pin "16") (pinfunction "AVDD_BIAS_16") (pintype "bidirectional"))
      (node (ref "U2") (pin "20") (pinfunction "AVDD1_20") (pintype "bidirectional"))
      (node (ref "U2") (pin "23") (pinfunction "AVDD2_23") (pintype "bidirectional"))
      (node (ref "U2") (pin "26") (pinfunction "AVDD3_26") (pintype "bidirectional"))
      (node (ref "U2") (pin "27") (pinfunction "AVDD4_27") (pintype "bidirectional"))
      (node (ref "U2") (pin "28") (pinfunction "AVDD5_28") (pintype "bidirectional"))
      (node (ref "U2") (pin "31") (pinfunction "AVDD6_31") (pintype "bidirectional"))
    )
    (net (code "8") (name "/AVDD_CODEC") (class "Default")
      (node (ref "C30") (pin "1") (pinfunction "1_1") (pintype "passive"))
      (node (ref "C31") (pin "1") (pinfunction "1_1") (pintype "passive"))
      (node (ref "C39") (pin "1") (pinfunction "1_1") (pintype "passive"))
      (node (ref "C64") (pin "1") (pinfunction "1_1") (pintype "passive"))
      (node (ref "C65") (pin "1") (pinfunction "1_1") (pintype "passive"))
      (node (ref "L15") (pin "1") (pinfunction "1_1") (pintype "passive"))
      (node (ref "L20") (pin "1") (pinfunction "1_1") (pintype "passive"))
      (node (ref "R10") (pin "2") (pinfunction "2_2") (pintype "passive"))
      (node (ref "R13") (pin "2") (pinfunction "2_2") (pintype "passive"))
      (node (ref "R16") (pin "2") (pinfunction "2_2") (pintype "passive"))
      (node (ref "U10") (pin "118") (pinfunction "VDDANA_118") (pintype "bidirectional"))
      (node (ref "U3") (pin "19") (pinfunction "VA_19") (pintype "bidirectional"))
      (node (ref "U4") (pin "6") (pinfunction "VDD_6") (pintype "bidirectional"))
    )
    (net (code "9") (name "/AVR_VDD") (class "Default")
      (node (ref "C32") (pin "1") (pinfunction "1_1") (pintype "passive"))
      (node (ref "C33") (pin "1") (pinfunction "1_1") (pintype "passive"))
      (node (ref "C34") (pin "1") (pinfunction "1_1") (pintype "passive"))
      (node (ref "C35") (pin "1") (pinfunction "1_1") (pintype "passive"))
      (node (ref "C37") (pin "1") (pinfunction "1_1") (pintype "passive"))
      (node (ref "C40") (pin "1") (pinfunction "1_1") (pintype "passive"))
      (node (ref "C41") (pin "1") (pinfunction "1_1") (pintype "passive"))
      (node (ref "C42") (pin "1") (pinfunction "1_1") (pintype "passive"))
      (node (ref "C43") (pin "1") (pinfunction "1_1") (pintype "passive"))
      (node (ref "C48") (pin "1") (pinfunction "1_1") (pintype "passive"))
      (node (ref "C49") (pin "1") (pinfunction "1_1") (pintype "passive"))
      (node (ref "C50") (pin "1") (pinfunction "1_1") (pintype "passive"))
      (node (ref "C51") (pin "1") (pinfunction "1_1") (pintype "passive"))
      (node (ref "C55") (pin "1") (pinfunction "1_1") (pintype "passive"))
      (node (ref "C56") (pin "1") (pinfunction "1_1") (pintype "passive"))
      (node (ref "C57") (pin "1") (pinfunction "1_1") (pintype "passive"))
      (node (ref "C58") (pin "1") (pinfunction "1_1") (pintype "passive"))
      (node (ref "C72") (pin "1") (pinfunction "1_1") (pintype "passive"))
      (node (ref "C74") (pin "1") (pinfunction "1_1") (pintype "passive"))
      (node (ref "C75") (pin "1") (pinfunction "1_1") (pintype "passive"))
      (node (ref "C77") (pin "1") (pinfunction "1_1") (pintype "passive"))
      (node (ref "C78") (pin "1") (pinfunction "1_1") (pintype "passive"))
      (node (ref "C95") (pin "1") (pinfunction "1_1") (pintype "passive"))
      (node (ref "JTAG") (pin "4") (pinfunction "4_4") (pintype "bidirectional"))
      (node (ref "L16") (pin "1") (pinfunction "1_1") (pintype "passive"))
      (node (ref "R18") (pin "2") (pinfunction "2_2") (pintype "passive"))
      (node (ref "R20") (pin "2") (pinfunction "2_2") (pintype "passive"))
      (node (ref "R22") (pin "2") (pinfunction "2_2") (pintype "passive"))
      (node (ref "R5") (pin "2") (pinfunction "2_2") (pintype "passive"))
      (node (ref "R8") (pin "2") (pinfunction "2_2") (pintype "passive"))
      (node (ref "SD1") (pin "VDD") (pinfunction "VDD_VDD") (pintype "bidirectional"))
      (node (ref "U10") (pin "10") (pinfunction "VDDIO_10") (pintype "bidirectional"))
      (node (ref "U10") (pin "103") (pinfunction "VDDIO_103") (pintype "bidirectional"))
      (node (ref "U10") (pin "130") (pinfunction "VDDIO_130") (pintype "bidirectional"))
      (node (ref "U10") (pin "142") (pinfunction "VDDIN_142") (pintype "bidirectional"))
      (node (ref "U10") (pin "143") (pinfunction "VDDIN_143") (pintype "bidirectional"))
      (node (ref "U10") (pin "2") (pinfunction "VDDIO_2") (pintype "bidirectional"))
      (node (ref "U10") (pin "21") (pinfunction "VDDIO_21") (pintype "bidirectional"))
      (node (ref "U10") (pin "48") (pinfunction "VDDIO_48") (pintype "bidirectional"))
      (node (ref "U10") (pin "64") (pinfunction "VDDIO_64") (pintype "bidirectional"))
      (node (ref "U10") (pin "81") (pinfunction "VDDIO_81") (pintype "bidirectional"))
    )
    (net (code "10") (name "/DVDD_CODEC") (class "Default")
      (node (ref "C28") (pin "1") (pinfunction "1_1") (pintype "passive"))
      (node (ref "C29") (pin "1") (pinfunction "1_1") (pintype "passive"))
      (node (ref "L14") (pin "1") (pinfunction "1_1") (pintype "passive"))
      (node (ref "U3") (pin "5") (pinfunction "VD_5") (pintype "bidirectional"))
      (node (ref "U3") (pin "8") (pinfunction "VLC_8") (pintype "bidirectional"))
    )
    (net (code "11") (name "/IOVDD") (class "Default")
      (node (ref "C11") (pin "1") (pinfunction "1_1") (pintype "passive"))
      (node (ref "C16") (pin "1") (pinfunction "1_1") (pintype "passive"))
      (node (ref "C17") (pin "1") (pinfunction "1_1") (pintype "passive"))
      (node (ref "C18") (pin "1") (pinfunction "1_1") (pintype "passive"))
      (node (ref "C2") (pin "1") (pinfunction "1_1") (pintype "passive"))
      (node (ref "C6") (pin "1") (pinfunction "1_1") (pintype "passive"))
      (node (ref "CC1") (pin "A") (pinfunction "A_A") (pintype "passive"))
      (node (ref "L3") (pin "1") (pinfunction "1_1") (pintype "passive"))
      (node (ref "U2") (pin "10") (pinfunction "IOVDD1_10") (pintype "bidirectional"))
      (node (ref "U2") (pin "12") (pinfunction "IOVDD2_12") (pintype "bidirectional"))
      (node (ref "U2") (pin "18") (pinfunction "IOVDD3_18") (pintype "bidirectional"))
      (node (ref "U2") (pin "37") (pinfunction "IOVDD4_37") (pintype "bidirectional"))
      (node (ref "U2") (pin "40") (pinfunction "DVDD_40") (pintype "bidirectional"))
    )
    (net (code "12") (name "/VBUS") (class "Default")
      (node (ref "C59") (pin "1") (pinfunction "1_1") (pintype "passive"))
      (node (ref "U10") (pin "1") (pinfunction "USB_VBUS_1") (pintype "bidirectional"))
      (node (ref "U6") (pin "1") (pinfunction "IN_1") (pintype "bidirectional"))
      (node (ref "USB") (pin "1") (pinfunction "VBUS_1") (pintype "bidirectional"))
    )
    (net (code "13") (name "/~{AVR_LED0}") (class "Default")
      (node (ref "AVR") (pin "C") (pinfunction "C_C") (pintype "passive"))
      (node (ref "U10") (pin "50") (pinfunction "PX08_50") (pintype "bidirectional"))
    )
    (net (code "14") (name "/~{AVR_LED1}") (class "Default")
      (node (ref "AVR1") (pin "C") (pinfunction "C_C") (pintype "passive"))
      (node (ref "U10") (pin "40") (pinfunction "PX15_40") (pintype "bidirectional"))
    )
    (net (code "15") (name "/~{CHANGE}") (class "Default")
      (node (ref "TO_AUX2") (pin "9") (pinfunction "9_9") (pintype "bidirectional"))
      (node (ref "U10") (pin "34") (pinfunction "PX12_34") (pintype "bidirectional"))
    )
    (net (code "16") (name "/~{CS_CC8531}") (class "Default")
      (node (ref "CC_DEBUG") (pin "5") (pinfunction "5_5") (pintype "bidirectional"))
      (node (ref "U10") (pin "133") (pinfunction "PA07_133") (pintype "bidirectional"))
      (node (ref "U2") (pin "3") (pinfunction "~{CS}_3") (pintype "bidirectional"))
    )
    (net (code "17") (name "/~{CS_CLOCK}") (class "Default")
      (node (ref "U10") (pin "100") (pinfunction "PA14_100") (pintype "bidirectional"))
      (node (ref "U9") (pin "8") (pinfunction "AD0/~{CS}_8") (pintype "bidirectional"))
    )
    (net (code "18") (name "/~{CS_CODEC}") (class "Default")
      (node (ref "U10") (pin "93") (pinfunction "PX32_93") (pintype "bidirectional"))
      (node (ref "U3") (pin "11") (pinfunction "AD0/~{CS}_11") (pintype "bidirectional"))
    )
    (net (code "19") (name "/~{CS_TOUCH}") (class "Default")
      (node (ref "TO_AUX2") (pin "7") (pinfunction "7_7") (pintype "bidirectional"))
      (node (ref "U10") (pin "51") (pinfunction "PX38_51") (pintype "bidirectional"))
    )
    (net (code "20") (name "/~{GPIO}") (class "Default")
      (node (ref "GPIO") (pin "2") (pinfunction "2_2") (pintype "bidirectional"))
      (node (ref "U10") (pin "74") (pinfunction "PX46_74") (pintype "bidirectional"))
    )
    (net (code "21") (name "/~{MUTE_L}") (class "Default")
      (node (ref "U10") (pin "96") (pinfunction "PX30_96") (pintype "bidirectional"))
      (node (ref "U3") (pin "21") (pinfunction "~{MUTEA}_21") (pintype "bidirectional"))
    )
    (net (code "22") (name "/~{MUTE_R}") (class "Default")
      (node (ref "U10") (pin "95") (pinfunction "PX33_95") (pintype "bidirectional"))
      (node (ref "U3") (pin "24") (pinfunction "~{MUTEB}_24") (pintype "bidirectional"))
    )
    (net (code "23") (name "/~{PAIR}") (class "Default")
      (node (ref "U10") (pin "129") (pinfunction "PA13_129") (pintype "bidirectional"))
      (node (ref "U2") (pin "7") (pinfunction "GIO1_7") (pintype "bidirectional"))
    )
    (net (code "24") (name "/~{RESET_CC8531}") (class "Default")
      (node (ref "CC_DEBUG") (pin "7") (pinfunction "7_7") (pintype "bidirectional"))
      (node (ref "L7") (pin "2") (pinfunction "2_2") (pintype "passive"))
      (node (ref "U10") (pin "127") (pinfunction "PA06_127") (pintype "bidirectional"))
    )
    (net (code "25") (name "/~{RESET_CODEC}") (class "Default")
      (node (ref "U10") (pin "97") (pinfunction "PX31_97") (pintype "bidirectional"))
      (node (ref "U3") (pin "14") (pinfunction "~{RESET}_14") (pintype "bidirectional"))
    )
    (net (code "26") (name "/~{RESET}") (class "Default")
      (node (ref "C73") (pin "1") (pinfunction "1_1") (pintype "passive"))
      (node (ref "JTAG") (pin "6") (pinfunction "6_6") (pintype "bidirectional"))
      (node (ref "R18") (pin "1") (pinfunction "1_1") (pintype "passive"))
      (node (ref "RESET") (pin "1") (pinfunction "1_1") (pintype "bidirectional"))
      (node (ref "U10") (pin "106") (pinfunction "~{RESET}_106") (pintype "bidirectional"))
    )
    (net (code "27") (name "/~{SD_CARD}") (class "Default")
      (node (ref "SD1") (pin "SWB") (pinfunction "SWB_SWB") (pintype "bidirectional"))
      (node (ref "U10") (pin "27") (pinfunction "PB01_27") (pintype "bidirectional"))
    )
    (net (code "28") (name "A3.3V") (class "Default")
      (node (ref "C70") (pin "1") (pinfunction "1_1") (pintype "passive"))
      (node (ref "L15") (pin "2") (pinfunction "2_2") (pintype "passive"))
      (node (ref "L20") (pin "2") (pinfunction "2_2") (pintype "passive"))
      (node (ref "U7") (pin "5") (pinfunction "VOUT_5") (pintype "bidirectional"))
    )
    (net (code "29") (name "AGND") (class "Default")
      (node (ref "C30") (pin "2") (pinfunction "2_2") (pintype "passive"))
      (node (ref "C31") (pin "2") (pinfunction "2_2") (pintype "passive"))
      (node (ref "C39") (pin "2") (pinfunction "2_2") (pintype "passive"))
      (node (ref "C44") (pin "2") (pinfunction "2_2") (pintype "passive"))
      (node (ref "C45") (pin "2") (pinfunction "2_2") (pintype "passive"))
      (node (ref "C46") (pin "2") (pinfunction "2_2") (pintype "passive"))
      (node (ref "C47") (pin "2") (pinfunction "2_2") (pintype "passive"))
      (node (ref "C63") (pin "2") (pinfunction "2_2") (pintype "passive"))
      (node (ref "C64") (pin "2") (pinfunction "2_2") (pintype "passive"))
      (node (ref "C65") (pin "2") (pinfunction "2_2") (pintype "passive"))
      (node (ref "C70") (pin "2") (pinfunction "2_2") (pintype "passive"))
      (node (ref "C71") (pin "2") (pinfunction "2_2") (pintype "passive"))
      (node (ref "C98") (pin "2") (pinfunction "2_2") (pintype "passive"))
      (node (ref "C99") (pin "2") (pinfunction "2_2") (pintype "passive"))
      (node (ref "LINE_IN") (pin "5") (pinfunction "GND_5") (pintype "bidirectional"))
      (node (ref "PHONE_OUT") (pin "5") (pinfunction "GND_5") (pintype "bidirectional"))
      (node (ref "R19") (pin "1") (pinfunction "1_1") (pintype "passive"))
      (node (ref "R24") (pin "2") (pinfunction "2_2") (pintype "passive"))
      (node (ref "R25") (pin "1") (pinfunction "1_1") (pintype "passive"))
      (node (ref "U10") (pin "117") (pinfunction "GNDANA_117") (pintype "bidirectional"))
      (node (ref "U3") (pin "20") (pinfunction "AGND_20") (pintype "bidirectional"))
      (node (ref "U4") (pin "2") (pinfunction "VSS_2") (pintype "bidirectional"))
      (node (ref "U7") (pin "2") (pinfunction "GND_2") (pintype "bidirectional"))
    )
    (net (code "30") (name "AUDIO") (class "Default")
      (node (ref "C53") (pin "1") (pinfunction "1_1") (pintype "passive"))
      (node (ref "R7") (pin "1") (pinfunction "1_1") (pintype "passive"))
      (node (ref "U10") (pin "116") (pinfunction "PA17_116") (pintype "bidirectional"))
      (node (ref "U4") (pin "7") (pinfunction "OUTA_7") (pintype "bidirectional"))
    )
    (net (code "31") (name "AUX_BLUE_BOT") (class "Default")
      (node (ref "Q7") (pin "1") (pinfunction "G_1") (pintype "passive"))
      (node (ref "TO_MAIN2") (pin "7") (pinfunction "7_7") (pintype "bidirectional"))
    )
    (net (code "32") (name "AUX_BLUE_TOP") (class "Default")
      (node (ref "Q6") (pin "1") (pinfunction "G_1") (pintype "passive"))
      (node (ref "TO_MAIN2") (pin "4") (pinfunction "4_4") (pintype "bidirectional"))
    )
    (net (code "33") (name "AUX_CS") (class "Default")
      (node (ref "TO_MAIN1") (pin "8") (pinfunction "8_8") (pintype "bidirectional"))
      (node (ref "U11") (pin "14") (pinfunction "~{SS}_14") (pintype "bidirectional"))
    )
    (net (code "34") (name "AUX_GREEN_BOT") (class "Default")
      (node (ref "Q5") (pin "1") (pinfunction "G_1") (pintype "passive"))
      (node (ref "TO_MAIN2") (pin "5") (pinfunction "5_5") (pintype "bidirectional"))
    )
    (net (code "35") (name "AUX_GREEN_TOP") (class "Default")
      (node (ref "Q4") (pin "1") (pinfunction "G_1") (pintype "passive"))
      (node (ref "TO_MAIN2") (pin "6") (pinfunction "6_6") (pintype "bidirectional"))
    )
    (net (code "36") (name "AUX_MISO") (class "Default")
      (node (ref "TO_MAIN1") (pin "4") (pinfunction "4_4") (pintype "bidirectional"))
      (node (ref "U11") (pin "16") (pinfunction "MISO_16") (pintype "bidirectional"))
    )
    (net (code "37") (name "AUX_MOSI") (class "Default")
      (node (ref "TO_MAIN1") (pin "6") (pinfunction "6_6") (pintype "bidirectional"))
      (node (ref "U11") (pin "15") (pinfunction "MOSI_15") (pintype "bidirectional"))
    )
    (net (code "38") (name "AUX_RED_BOT") (class "Default")
      (node (ref "Q3") (pin "1") (pinfunction "G_1") (pintype "passive"))
      (node (ref "TO_MAIN2") (pin "3") (pinfunction "3_3") (pintype "bidirectional"))
    )
    (net (code "39") (name "AUX_RED_TOP") (class "Default")
      (node (ref "Q2") (pin "1") (pinfunction "G_1") (pintype "passive"))
      (node (ref "TO_MAIN2") (pin "8") (pinfunction "8_8") (pintype "bidirectional"))
    )
    (net (code "40") (name "AUX_SCLK") (class "Default")
      (node (ref "TO_MAIN1") (pin "2") (pinfunction "2_2") (pintype "bidirectional"))
      (node (ref "U11") (pin "17") (pinfunction "SCK_17") (pintype "bidirectional"))
    )
    (net (code "41") (name "BAT") (class "Default")
      (node (ref "BATTERY") (pin "+") (pinfunction "P_+") (pintype "passive"))
      (node (ref "C60") (pin "1") (pinfunction "1_1") (pintype "passive"))
      (node (ref "F1") (pin "1") (pinfunction "1_1") (pintype "passive"))
      (node (ref "R11") (pin "2") (pinfunction "2_2") (pintype "passive"))
      (node (ref "U2") (pin "29") (pinfunction "VBAT_29") (pintype "bidirectional"))
      (node (ref "U6") (pin "10") (pinfunction "OUT_10") (pintype "bidirectional"))
    )
    (net (code "42") (name "BCLK") (class "Default")
      (node (ref "L9") (pin "1") (pinfunction "1_1") (pintype "passive"))
      (node (ref "U10") (pin "38") (pinfunction "PX35_38") (pintype "bidirectional"))
      (node (ref "U10") (pin "61") (pinfunction "PX34_61") (pintype "bidirectional"))
      (node (ref "U10") (pin "85") (pinfunction "PX23_85") (pintype "bidirectional"))
      (node (ref "U10") (pin "91") (pinfunction "PX28_91") (pintype "bidirectional"))
      (node (ref "U3") (pin "4") (pinfunction "BCLK_4") (pintype "bidirectional"))
    )
    (net (code "43") (name "BLUE_BOT") (class "Default")
      (node (ref "TO_AUX1") (pin "8") (pinfunction "8_8") (pintype "bidirectional"))
      (node (ref "U10") (pin "84") (pinfunction "PX18_84") (pintype "bidirectional"))
    )
    (net (code "44") (name "BLUE_TOP") (class "Default")
      (node (ref "TO_AUX1") (pin "3") (pinfunction "3_3") (pintype "bidirectional"))
      (node (ref "U10") (pin "68") (pinfunction "PX14_68") (pintype "bidirectional"))
    )
    (net (code "45") (name "CTS") (class "Default")
      (node (ref "SERIAL") (pin "5") (pinfunction "5_5") (pintype "bidirectional"))
      (node (ref "U10") (pin "62") (pinfunction "PX02_62") (pintype "bidirectional"))
    )
    (net (code "46") (name "D+_UC") (class "Default")
      (node (ref "R15") (pin "2") (pinfunction "2_2") (pintype "passive"))
      (node (ref "U10") (pin "6") (pinfunction "D+_HS_6") (pintype "bidirectional"))
      (node (ref "USB") (pin "3") (pinfunction "D+_3") (pintype "bidirectional"))
    )
    (net (code "47") (name "D-_UC") (class "Default")
      (node (ref "R17") (pin "2") (pinfunction "2_2") (pintype "passive"))
      (node (ref "U10") (pin "5") (pinfunction "D-_HS_5") (pintype "bidirectional"))
      (node (ref "USB") (pin "2") (pinfunction "D-_2") (pintype "bidirectional"))
    )
    (net (code "48") (name "D3.3V") (class "Default")
      (node (ref "C61") (pin "1") (pinfunction "1_1") (pintype "passive"))
      (node (ref "C79") (pin "1") (pinfunction "1_1") (pintype "passive"))
      (node (ref "C80") (pin "1") (pinfunction "1_1") (pintype "passive"))
      (node (ref "C81") (pin "1") (pinfunction "1_1") (pintype "passive"))
      (node (ref "CC_DEBUG") (pin "2") (pinfunction "2_2") (pintype "bidirectional"))
      (node (ref "L1") (pin "2") (pinfunction "2_2") (pintype "passive"))
      (node (ref "L14") (pin "2") (pinfunction "2_2") (pintype "passive"))
      (node (ref "L16") (pin "2") (pinfunction "2_2") (pintype "passive"))
      (node (ref "L17") (pin "2") (pinfunction "2_2") (pintype "passive"))
      (node (ref "L19") (pin "2") (pinfunction "2_2") (pintype "passive"))
      (node (ref "L2") (pin "2") (pinfunction "2_2") (pintype "passive"))
      (node (ref "L3") (pin "2") (pinfunction "2_2") (pintype "passive"))
      (node (ref "R12") (pin "2") (pinfunction "2_2") (pintype "passive"))
      (node (ref "U5") (pin "3") (pinfunction "VOUT_3") (pintype "bidirectional"))
      (node (ref "U8") (pin "5") (pinfunction "VCC_5") (pintype "bidirectional"))
      (node (ref "U9") (pin "1") (pinfunction "VD_1") (pintype "bidirectional"))
    )
    (net (code "49") (name "DAC0_N") (class "Default")
      (node (ref "U10") (pin "126") (pinfunction "PA04_126") (pintype "bidirectional"))
    )
    (net (code "50") (name "DAC0_P") (class "Default")
      (node (ref "U10") (pin "125") (pinfunction "PA03_125") (pintype "bidirectional"))
    )
    (net (code "51") (name "DAC1_N") (class "Default")
      (node (ref "U10") (pin "112") (pinfunction "PA24_112") (pintype "bidirectional"))
    )
    (net (code "52") (name "DAC1_P") (class "Default")
      (node (ref "U10") (pin "111") (pinfunction "PA23_111") (pintype "bidirectional"))
    )
    (net (code "53") (name "DGND") (class "Default")
      (node (ref "C1") (pin "2") (pinfunction "2_2") (pintype "passive"))
      (node (ref "C10") (pin "2") (pinfunction "2_2") (pintype "passive"))
      (node (ref "C11") (pin "2") (pinfunction "2_2") (pintype "passive"))
      (node (ref "C12") (pin "2") (pinfunction "2_2") (pintype "passive"))
      (node (ref "C13") (pin "2") (pinfunction "2_2") (pintype "passive"))
      (node (ref "C14") (pin "2") (pinfunction "2_2") (pintype "passive"))
      (node (ref "C15") (pin "2") (pinfunction "2_2") (pintype "passive"))
      (node (ref "C16") (pin "2") (pinfunction "2_2") (pintype "passive"))
      (node (ref "C17") (pin "2") (pinfunction "2_2") (pintype "passive"))
      (node (ref "C18") (pin "2") (pinfunction "2_2") (pintype "passive"))
      (node (ref "C19") (pin "2") (pinfunction "2_2") (pintype "passive"))
      (node (ref "C2") (pin "2") (pinfunction "2_2") (pintype "passive"))
      (node (ref "C20") (pin "2") (pinfunction "2_2") (pintype "passive"))
      (node (ref "C23") (pin "2") (pinfunction "2_2") (pintype "passive"))
      (node (ref "C24") (pin "2") (pinfunction "2_2") (pintype "passive"))
      (node (ref "C25") (pin "2") (pinfunction "2_2") (pintype "passive"))
      (node (ref "C26") (pin "2") (pinfunction "2_2") (pintype "passive"))
      (node (ref "C27") (pin "2") (pinfunction "2_2") (pintype "passive"))
      (node (ref "C28") (pin "2") (pinfunction "2_2") (pintype "passive"))
      (node (ref "C29") (pin "2") (pinfunction "2_2") (pintype "passive"))
      (node (ref "C3") (pin "2") (pinfunction "2_2") (pintype "passive"))
      (node (ref "C32") (pin "2") (pinfunction "2_2") (pintype "passive"))
      (node (ref "C33") (pin "2") (pinfunction "2_2") (pintype "passive"))
      (node (ref "C34") (pin "2") (pinfunction "2_2") (pintype "passive"))
      (node (ref "C35") (pin "2") (pinfunction "2_2") (pintype "passive"))
      (node (ref "C37") (pin "2") (pinfunction "2_2") (pintype "passive"))
      (node (ref "C4") (pin "2") (pinfunction "2_2") (pintype "passive"))
      (node (ref "C40") (pin "2") (pinfunction "2_2") (pintype "passive"))
      (node (ref "C41") (pin "2") (pinfunction "2_2") (pintype "passive"))
      (node (ref "C42") (pin "2") (pinfunction "2_2") (pintype "passive"))
      (node (ref "C43") (pin "2") (pinfunction "2_2") (pintype "passive"))
      (node (ref "C48") (pin "2") (pinfunction "2_2") (pintype "passive"))
      (node (ref "C49") (pin "2") (pinfunction "2_2") (pintype "passive"))
      (node (ref "C5") (pin "2") (pinfunction "2_2") (pintype "passive"))
      (node (ref "C50") (pin "2") (pinfunction "2_2") (pintype "passive"))
      (node (ref "C51") (pin "2") (pinfunction "2_2") (pintype "passive"))
      (node (ref "C54") (pin "2") (pinfunction "2_2") (pintype "passive"))
      (node (ref "C55") (pin "2") (pinfunction "2_2") (pintype "passive"))
      (node (ref "C56") (pin "2") (pinfunction "2_2") (pintype "passive"))
      (node (ref "C57") (pin "2") (pinfunction "2_2") (pintype "passive"))
      (node (ref "C58") (pin "2") (pinfunction "2_2") (pintype "passive"))
      (node (ref "C6") (pin "2") (pinfunction "2_2") (pintype "passive"))
      (node (ref "C61") (pin "2") (pinfunction "2_2") (pintype "passive"))
      (node (ref "C62") (pin "2") (pinfunction "2_2") (pintype "passive"))
      (node (ref "C68") (pin "2") (pinfunction "2_2") (pintype "passive"))
      (node (ref "C69") (pin "2") (pinfunction "2_2") (pintype "passive"))
      (node (ref "C7") (pin "2") (pinfunction "2_2") (pintype "passive"))
      (node (ref "C72") (pin "2") (pinfunction "2_2") (pintype "passive"))
      (node (ref "C73") (pin "2") (pinfunction "2_2") (pintype "passive"))
      (node (ref "C74") (pin "2") (pinfunction "2_2") (pintype "passive"))
      (node (ref "C75") (pin "2") (pinfunction "2_2") (pintype "passive"))
      (node (ref "C76") (pin "2") (pinfunction "2_2") (pintype "passive"))
      (node (ref "C77") (pin "2") (pinfunction "2_2") (pintype "passive"))
      (node (ref "C78") (pin "2") (pinfunction "2_2") (pintype "passive"))
      (node (ref "C79") (pin "2") (pinfunction "2_2") (pintype "passive"))
      (node (ref "C8") (pin "2") (pinfunction "2_2") (pintype "passive"))
      (node (ref "C80") (pin "2") (pinfunction "2_2") (pintype "passive"))
      (node (ref "C81") (pin "2") (pinfunction "2_2") (pintype "passive"))
      (node (ref "C82") (pin "2") (pinfunction "2_2") (pintype "passive"))
      (node (ref "C83") (pin "2") (pinfunction "2_2") (pintype "passive"))
      (node (ref "C84") (pin "2") (pinfunction "2_2") (pintype "passive"))
      (node (ref "C9") (pin "2") (pinfunction "2_2") (pintype "passive"))
      (node (ref "C95") (pin "2") (pinfunction "2_2") (pintype "passive"))
      (node (ref "CC_DEBUG") (pin "1") (pinfunction "1_1") (pintype "bidirectional"))
      (node (ref "GPIO") (pin "4") (pinfunction "4_4") (pintype "bidirectional"))
      (node (ref "JTAG") (pin "10") (pinfunction "10_10") (pintype "bidirectional"))
      (node (ref "JTAG") (pin "2") (pinfunction "2_2") (pintype "bidirectional"))
      (node (ref "L6") (pin "1") (pinfunction "1_1") (pintype "passive"))
      (node (ref "POWER") (pin "C") (pinfunction "C_C") (pintype "passive"))
      (node (ref "R2") (pin "1") (pinfunction "1_1") (pintype "passive"))
      (node (ref "R26") (pin "2") (pinfunction "2_2") (pintype "passive"))
      (node (ref "R27") (pin "1") (pinfunction "1_1") (pintype "passive"))
      (node (ref "R3") (pin "1") (pinfunction "1_1") (pintype "passive"))
      (node (ref "R6") (pin "1") (pinfunction "1_1") (pintype "passive"))
      (node (ref "RESET") (pin "3") (pinfunction "3_3") (pintype "bidirectional"))
      (node (ref "SD1") (pin "GND1") (pinfunction "GND_GND1") (pintype "bidirectional"))
      (node (ref "SD1") (pin "GND2") (pinfunction "GND_GND2") (pintype "bidirectional"))
      (node (ref "SD1") (pin "GND3") (pinfunction "GND_GND3") (pintype "bidirectional"))
      (node (ref "SD1") (pin "GND4") (pinfunction "GND_GND4") (pintype "bidirectional"))
      (node (ref "SD1") (pin "SWA") (pinfunction "SWA_SWA") (pintype "bidirectional"))
      (node (ref "SD1") (pin "VSS") (pinfunction "GND_VSS") (pintype "bidirectional"))
      (node (ref "SERIAL") (pin "6") (pinfunction "6_6") (pintype "bidirectional"))
      (node (ref "SMA") (pin "GND1") (pinfunction "GND_GND1") (pintype "bidirectional"))
      (node (ref "SMA") (pin "GND2") (pinfunction "GND_GND2") (pintype "bidirectional"))
      (node (ref "SMA") (pin "GND3") (pinfunction "GND_GND3") (pintype "bidirectional"))
      (node (ref "SMA") (pin "GND4") (pinfunction "GND_GND4") (pintype "bidirectional"))
      (node (ref "TO_AUX1") (pin "10") (pinfunction "10_10") (pintype "bidirectional"))
      (node (ref "TO_AUX1") (pin "9") (pinfunction "9_9") (pintype "bidirectional"))
      (node (ref "TO_AUX2") (pin "10") (pinfunction "10_10") (pintype "bidirectional"))
      (node (ref "TO_AUX2") (pin "6") (pinfunction "6_6") (pintype "bidirectional"))
      (node (ref "TO_AUX2") (pin "8") (pinfunction "8_8") (pintype "bidirectional"))
      (node (ref "U1") (pin "12") (pinfunction "GND_12") (pintype "bidirectional"))
      (node (ref "U1") (pin "14") (pinfunction "GND_14") (pintype "bidirectional"))
      (node (ref "U1") (pin "8") (pinfunction "GND_8") (pintype "bidirectional"))
      (node (ref "U1") (pin "9") (pinfunction "GND_9") (pintype "bidirectional"))
      (node (ref "U1") (pin "GND") (pinfunction "GND_GND") (pintype "bidirectional"))
      (node (ref "U10") (pin "102") (pinfunction "GNDIO_102") (pintype "bidirectional"))
      (node (ref "U10") (pin "131") (pinfunction "GNDIO_131") (pintype "bidirectional"))
      (node (ref "U10") (pin "140") (pinfunction "GNDCORE_140") (pintype "bidirectional"))
      (node (ref "U10") (pin "144") (pinfunction "GNDPLL_144") (pintype "bidirectional"))
      (node (ref "U10") (pin "20") (pinfunction "GNDIO_20") (pintype "bidirectional"))
      (node (ref "U10") (pin "4") (pinfunction "GNDIO_4") (pintype "bidirectional"))
      (node (ref "U10") (pin "47") (pinfunction "GNDIO_47") (pintype "bidirectional"))
      (node (ref "U10") (pin "65") (pinfunction "GNDIO_65") (pintype "bidirectional"))
      (node (ref "U10") (pin "7") (pinfunction "GNDIO_7") (pintype "bidirectional"))
      (node (ref "U10") (pin "82") (pinfunction "GNDIO_82") (pintype "bidirectional"))
      (node (ref "U2") (pin "19") (pinfunction "AD2/GIO9_19") (pintype "bidirectional"))
      (node (ref "U2") (pin "32") (pinfunction "SCL/GIO10_32") (pintype "bidirectional"))
      (node (ref "U2") (pin "33") (pinfunction "SDA/GIO11_33") (pintype "bidirectional"))
      (node (ref "U2") (pin "34") (pinfunction "GIO12_34") (pintype "bidirectional"))
      (node (ref "U2") (pin "35") (pinfunction "GIO13_35") (pintype "bidirectional"))
      (node (ref "U2") (pin "GND") (pinfunction "GND_GND") (pintype "bidirectional"))
      (node (ref "U3") (pin "6") (pinfunction "DGND_6") (pintype "bidirectional"))
      (node (ref "U5") (pin "2") (pinfunction "GND_2") (pintype "bidirectional"))
      (node (ref "U5") (pin "4") (pinfunction "GND_4") (pintype "bidirectional"))
      (node (ref "U8") (pin "3") (pinfunction "GND_3") (pintype "bidirectional"))
      (node (ref "U9") (pin "2") (pinfunction "GND_2") (pintype "bidirectional"))
      (node (ref "U9") (pin "7") (pinfunction "FILTN_7") (pintype "bidirectional"))
      (node (ref "X1") (pin "2") (pinfunction "CASE_2") (pintype "passive"))
      (node (ref "X1") (pin "4") (pinfunction "CASE_4") (pintype "passive"))
      (node (ref "X2") (pin "GND-1") (pinfunction "CASE_GND-1") (pintype "passive"))
      (node (ref "X2") (pin "GND-2") (pinfunction "CASE_GND-2") (pintype "passive"))
    )
    (net (code "54") (name "DIN") (class "Default")
      (node (ref "L13") (pin "1") (pinfunction "1_1") (pintype "passive"))
      (node (ref "U10") (pin "86") (pinfunction "PX24_86") (pintype "bidirectional"))
      (node (ref "U3") (pin "1") (pinfunction "DIN_1") (pintype "bidirectional"))
    )
    (net (code "55") (name "DOUT") (class "Default")
      (node (ref "L11") (pin "1") (pinfunction "1_1") (pintype "passive"))
      (node (ref "U10") (pin "92") (pinfunction "PX25_92") (pintype "bidirectional"))
      (node (ref "U3") (pin "7") (pinfunction "DOUT_7") (pintype "bidirectional"))
    )
    (net (code "56") (name "GREEN_BOT") (class "Default")
      (node (ref "TO_AUX1") (pin "6") (pinfunction "6_6") (pintype "bidirectional"))
      (node (ref "U10") (pin "139") (pinfunction "PA09_139") (pintype "bidirectional"))
    )
    (net (code "57") (name "GREEN_TOP") (class "Default")
      (node (ref "TO_AUX1") (pin "5") (pinfunction "5_5") (pintype "bidirectional"))
      (node (ref "U10") (pin "75") (pinfunction "PX50_75") (pintype "bidirectional"))
    )
    (net (code "58") (name "IN_L") (class "Default")
      (node (ref "C38") (pin "1") (pinfunction "1_1") (pintype "passive"))
      (node (ref "LINE_IN") (pin "4") (pinfunction "L_4") (pintype "bidirectional"))
      (node (ref "R19") (pin "2") (pinfunction "2_2") (pintype "passive"))
    )
    (net (code "59") (name "IN_R") (class "Default")
      (node (ref "C36") (pin "1") (pinfunction "1_1") (pintype "passive"))
      (node (ref "LINE_IN") (pin "1") (pinfunction "R_1") (pintype "bidirectional"))
    )
    (net (code "60") (name "LINEIN_SENSE") (class "Default")
      (node (ref "LINE_IN") (pin "3") (pinfunction "L_SW_3") (pintype "bidirectional"))
      (node (ref "R13") (pin "1") (pinfunction "1_1") (pintype "passive"))
      (node (ref "U10") (pin "114") (pinfunction "PA19_114") (pintype "bidirectional"))
    )
    (net (code "61") (name "LNA_EN") (class "Default")
      (node (ref "U1") (pin "6") (pinfunction "EN_6") (pintype "bidirectional"))
      (node (ref "U2") (pin "38") (pinfunction "XLNAEN_38") (pintype "bidirectional"))
    )
    (net (code "62") (name "MCI-CLK") (class "Default")
      (node (ref "SD1") (pin "CLK") (pinfunction "CLK/SCLK_CLK") (pintype "bidirectional"))
      (node (ref "U10") (pin "26") (pinfunction "PA27_26") (pintype "bidirectional"))
    )
    (net (code "63") (name "MCI-CMD") (class "Default")
      (node (ref "R22") (pin "1") (pinfunction "1_1") (pintype "passive"))
      (node (ref "SD1") (pin "CMD") (pinfunction "CMD/MOSI_CMD") (pintype "bidirectional"))
      (node (ref "U10") (pin "28") (pinfunction "PA28_28") (pintype "bidirectional"))
    )
    (net (code "64") (name "MCI-DATA0") (class "Default")
      (node (ref "R20") (pin "1") (pinfunction "1_1") (pintype "passive"))
      (node (ref "SD1") (pin "DAT0") (pinfunction "DAT0/MISO_DAT0") (pintype "bidirectional"))
      (node (ref "U10") (pin "23") (pinfunction "PA29_23") (pintype "bidirectional"))
    )
    (net (code "65") (name "MCI-DATA1") (class "Default")
      (node (ref "SD1") (pin "DAT1") (pinfunction "DAT1/NC_DAT1") (pintype "bidirectional"))
      (node (ref "U10") (pin "14") (pinfunction "PA30_14") (pintype "bidirectional"))
    )
    (net (code "66") (name "MCI-DATA2") (class "Default")
      (node (ref "SD1") (pin "DAT2") (pinfunction "DAT2/NC_DAT2") (pintype "bidirectional"))
      (node (ref "U10") (pin "29") (pinfunction "PA31_29") (pintype "bidirectional"))
    )
    (net (code "67") (name "MCI-DATA3") (class "Default")
      (node (ref "SD1") (pin "CD/DAT3") (pinfunction "CD/DAT3/~{CS}_CD/DAT3") (pintype "bidirectional"))
      (node (ref "U10") (pin "30") (pinfunction "PB00_30") (pintype "bidirectional"))
    )
    (net (code "68") (name "MCLK") (class "Default")
      (node (ref "L8") (pin "1") (pinfunction "1_1") (pintype "passive"))
      (node (ref "U3") (pin "3") (pinfunction "MCLK_3") (pintype "bidirectional"))
      (node (ref "U8") (pin "2") (pinfunction "CLK_2") (pintype "bidirectional"))
      (node (ref "U9") (pin "3") (pinfunction "CLK_OUT_3") (pintype "bidirectional"))
    )
    (net (code "69") (name "MISO0") (class "Default")
      (node (ref "CC_DEBUG") (pin "10") (pinfunction "10_10") (pintype "bidirectional"))
      (node (ref "U10") (pin "136") (pinfunction "PA11_136") (pintype "bidirectional"))
      (node (ref "U2") (pin "6") (pinfunction "MISO_6") (pintype "bidirectional"))
      (node (ref "U3") (pin "9") (pinfunction "SDA/MISO_9") (pintype "bidirectional"))
    )
    (net (code "70") (name "MISO1") (class "Default")
      (node (ref "TO_AUX2") (pin "3") (pinfunction "3_3") (pintype "bidirectional"))
      (node (ref "U10") (pin "11") (pinfunction "PB08_11") (pintype "bidirectional"))
    )
    (net (code "71") (name "MOSI0") (class "Default")
      (node (ref "CC_DEBUG") (pin "8") (pinfunction "8_8") (pintype "bidirectional"))
      (node (ref "U10") (pin "138") (pinfunction "PA10_138") (pintype "bidirectional"))
      (node (ref "U2") (pin "5") (pinfunction "MOSI_5") (pintype "bidirectional"))
      (node (ref "U3") (pin "12") (pinfunction "AD1/MOSI_12") (pintype "bidirectional"))
      (node (ref "U9") (pin "10") (pinfunction "SDA/MOSI_10") (pintype "bidirectional"))
    )
    (net (code "72") (name "MOSI1") (class "Default")
      (node (ref "TO_AUX2") (pin "5") (pinfunction "5_5") (pintype "bidirectional"))
      (node (ref "U10") (pin "16") (pinfunction "PB10_16") (pintype "bidirectional"))
    )
    (net (code "73") (name "Net-(AVR-PadA)") (class "Default")
      (node (ref "AVR") (pin "A") (pinfunction "A_A") (pintype "passive"))
      (node (ref "R8") (pin "1") (pinfunction "1_1") (pintype "passive"))
    )
    (net (code "74") (name "Net-(AVR1-PadA)") (class "Default")
      (node (ref "AVR1") (pin "A") (pinfunction "A_A") (pintype "passive"))
      (node (ref "R5") (pin "1") (pinfunction "1_1") (pintype "passive"))
    )
    (net (code "75") (name "Net-(BUTTON-PadP$1)") (class "Default")
      (node (ref "BUTTON") (pin "P$1") (pinfunction "P$1_P$1") (pintype "bidirectional"))
      (node (ref "R31") (pin "2") (pinfunction "2_2") (pintype "passive"))
    )
    (net (code "76") (name "Net-(C21-Pad1)") (class "Default")
      (node (ref "C21") (pin "1") (pinfunction "1_1") (pintype "passive"))
      (node (ref "L5") (pin "2") (pinfunction "2_2") (pintype "passive"))
    )
    (net (code "77") (name "Net-(C21-Pad2)") (class "Default")
      (node (ref "C21") (pin "2") (pinfunction "2_2") (pintype "passive"))
      (node (ref "C22") (pin "1") (pinfunction "1_1") (pintype "passive"))
      (node (ref "C24") (pin "1") (pinfunction "1_1") (pintype "passive"))
      (node (ref "L6") (pin "2") (pinfunction "2_2") (pintype "passive"))
    )
    (net (code "78") (name "Net-(C22-Pad2)") (class "Default")
      (node (ref "C22") (pin "2") (pinfunction "2_2") (pintype "passive"))
      (node (ref "SMA") (pin "SIG") (pinfunction "SIG_SIG") (pintype "bidirectional"))
    )
    (net (code "79") (name "Net-(C23-Pad1)") (class "Default")
      (node (ref "C23") (pin "1") (pinfunction "1_1") (pintype "passive"))
      (node (ref "L4") (pin "2") (pinfunction "2_2") (pintype "passive"))
      (node (ref "L5") (pin "1") (pinfunction "1_1") (pintype "passive"))
    )
    (net (code "80") (name "Net-(C52-Pad1)") (class "Default")
      (node (ref "C52") (pin "1") (pinfunction "1_1") (pintype "passive"))
      (node (ref "R41") (pin "1") (pinfunction "1_1") (pintype "passive"))
    )
    (net (code "81") (name "Net-(C52-Pad2)") (class "Default")
      (node (ref "C52") (pin "2") (pinfunction "2_2") (pintype "passive"))
      (node (ref "C98") (pin "1") (pinfunction "1_1") (pintype "passive"))
      (node (ref "R9") (pin "2") (pinfunction "2_2") (pintype "passive"))
    )
    (net (code "82") (name "Net-(C54-Pad1)") (class "Default")
      (node (ref "C54") (pin "1") (pinfunction "1_1") (pintype "passive"))
      (node (ref "L17") (pin "1") (pinfunction "1_1") (pintype "passive"))
      (node (ref "TO_AUX1") (pin "1") (pinfunction "1_1") (pintype "bidirectional"))
      (node (ref "TO_AUX1") (pin "2") (pinfunction "2_2") (pintype "bidirectional"))
    )
    (net (code "83") (name "Net-(C62-Pad1)") (class "Default")
      (node (ref "C62") (pin "1") (pinfunction "1_1") (pintype "passive"))
      (node (ref "L19") (pin "1") (pinfunction "1_1") (pintype "passive"))
      (node (ref "TO_AUX2") (pin "2") (pinfunction "2_2") (pintype "bidirectional"))
      (node (ref "TO_AUX2") (pin "4") (pinfunction "4_4") (pintype "bidirectional"))
    )
    (net (code "84") (name "Net-(C67-Pad1)") (class "Default")
      (node (ref "C67") (pin "1") (pinfunction "1_1") (pintype "passive"))
      (node (ref "R40") (pin "1") (pinfunction "1_1") (pintype "passive"))
    )
    (net (code "85") (name "Net-(C67-Pad2)") (class "Default")
      (node (ref "C67") (pin "2") (pinfunction "2_2") (pintype "passive"))
      (node (ref "C99") (pin "1") (pinfunction "1_1") (pintype "passive"))
      (node (ref "R14") (pin "2") (pinfunction "2_2") (pintype "passive"))
    )
    (net (code "86") (name "Net-(CC1-PadC)") (class "Default")
      (node (ref "CC1") (pin "C") (pinfunction "C_C") (pintype "passive"))
      (node (ref "R4") (pin "2") (pinfunction "2_2") (pintype "passive"))
    )
    (net (code "87") (name "Net-(CHARGE-PadA)") (class "Default")
      (node (ref "CHARGE") (pin "A") (pinfunction "A_A") (pintype "passive"))
      (node (ref "R11") (pin "1") (pinfunction "1_1") (pintype "passive"))
    )
    (net (code "88") (name "Net-(NEXT-PadP$1)") (class "Default")
      (node (ref "NEXT") (pin "P$1") (pinfunction "P$1_P$1") (pintype "bidirectional"))
      (node (ref "R30") (pin "2") (pinfunction "2_2") (pintype "passive"))
    )
    (net (code "89") (name "Net-(PLAY/PAUSE-PadP$1)") (class "Default")
      (node (ref "PLAY/PAUSE") (pin "P$1") (pinfunction "P$1_P$1") (pintype "bidirectional"))
      (node (ref "R36") (pin "2") (pinfunction "2_2") (pintype "passive"))
    )
    (net (code "90") (name "Net-(POWER-PadA)") (class "Default")
      (node (ref "POWER") (pin "A") (pinfunction "A_A") (pintype "passive"))
      (node (ref "R12") (pin "1") (pinfunction "1_1") (pintype "passive"))
    )
    (net (code "91") (name "Net-(PREV-PadP$1)") (class "Default")
      (node (ref "PREV") (pin "P$1") (pinfunction "P$1_P$1") (pintype "bidirectional"))
      (node (ref "R35") (pin "2") (pinfunction "2_2") (pintype "passive"))
    )
    (net (code "92") (name "Net-(Q2-D)") (class "Default")
      (node (ref "LED_UL") (pin "1") (pinfunction "KR_1") (pintype "passive"))
      (node (ref "LED_UL") (pin "1-2") (pinfunction "KR_1-2") (pintype "passive"))
      (node (ref "LED_UR") (pin "1") (pinfunction "KR_1") (pintype "passive"))
      (node (ref "LED_UR") (pin "1-2") (pinfunction "KR_1-2") (pintype "passive"))
      (node (ref "Q2") (pin "3") (pinfunction "D_3") (pintype "passive"))
    )
    (net (code "93") (name "Net-(Q3-D)") (class "Default")
      (node (ref "LED_LL") (pin "1") (pinfunction "KR_1") (pintype "passive"))
      (node (ref "LED_LL") (pin "1-2") (pinfunction "KR_1-2") (pintype "passive"))
      (node (ref "LED_LR") (pin "1") (pinfunction "KR_1") (pintype "passive"))
      (node (ref "LED_LR") (pin "1-2") (pinfunction "KR_1-2") (pintype "passive"))
      (node (ref "Q3") (pin "3") (pinfunction "D_3") (pintype "passive"))
    )
    (net (code "94") (name "Net-(Q4-D)") (class "Default")
      (node (ref "LED_UL") (pin "4") (pinfunction "KG_4") (pintype "passive"))
      (node (ref "LED_UL") (pin "4-2") (pinfunction "KG_4-2") (pintype "passive"))
      (node (ref "LED_UR") (pin "4") (pinfunction "KG_4") (pintype "passive"))
      (node (ref "LED_UR") (pin "4-2") (pinfunction "KG_4-2") (pintype "passive"))
      (node (ref "Q4") (pin "3") (pinfunction "D_3") (pintype "passive"))
    )
    (net (code "95") (name "Net-(Q5-D)") (class "Default")
      (node (ref "LED_LL") (pin "4") (pinfunction "KG_4") (pintype "passive"))
      (node (ref "LED_LL") (pin "4-2") (pinfunction "KG_4-2") (pintype "passive"))
      (node (ref "LED_LR") (pin "4") (pinfunction "KG_4") (pintype "passive"))
      (node (ref "LED_LR") (pin "4-2") (pinfunction "KG_4-2") (pintype "passive"))
      (node (ref "Q5") (pin "3") (pinfunction "D_3") (pintype "passive"))
    )
    (net (code "96") (name "Net-(Q6-D)") (class "Default")
      (node (ref "LED_UL") (pin "3") (pinfunction "KB_3") (pintype "passive"))
      (node (ref "LED_UL") (pin "3-2") (pinfunction "KB_3-2") (pintype "passive"))
      (node (ref "LED_UR") (pin "3") (pinfunction "KB_3") (pintype "passive"))
      (node (ref "LED_UR") (pin "3-2") (pinfunction "KB_3-2") (pintype "passive"))
      (node (ref "Q6") (pin "3") (pinfunction "D_3") (pintype "passive"))
    )
    (net (code "97") (name "Net-(Q7-D)") (class "Default")
      (node (ref "LED_LL") (pin "3") (pinfunction "KB_3") (pintype "passive"))
      (node (ref "LED_LL") (pin "3-2") (pinfunction "KB_3-2") (pintype "passive"))
      (node (ref "LED_LR") (pin "3") (pinfunction "KB_3") (pintype "passive"))
      (node (ref "LED_LR") (pin "3-2") (pinfunction "KB_3-2") (pintype "passive"))
      (node (ref "Q7") (pin "3") (pinfunction "D_3") (pintype "passive"))
    )
    (net (code "98") (name "Net-(R29-Pad2)") (class "Default")
      (node (ref "R29") (pin "2") (pinfunction "2_2") (pintype "passive"))
      (node (ref "STOP") (pin "P$1") (pinfunction "P$1_P$1") (pintype "bidirectional"))
    )
    (net (code "99") (name "Net-(R32-Pad2)") (class "Default")
      (node (ref "R32") (pin "2") (pinfunction "2_2") (pintype "passive"))
      (node (ref "VOL+") (pin "P$1") (pinfunction "P$1_P$1") (pintype "bidirectional"))
    )
    (net (code "100") (name "Net-(R33-Pad2)") (class "Default")
      (node (ref "R33") (pin "2") (pinfunction "2_2") (pintype "passive"))
      (node (ref "WIRELESS") (pin "P$1") (pinfunction "P$1_P$1") (pintype "bidirectional"))
    )
    (net (code "101") (name "Net-(R34-Pad2)") (class "Default")
      (node (ref "R34") (pin "2") (pinfunction "2_2") (pintype "passive"))
      (node (ref "VOL-") (pin "P$1") (pinfunction "P$1_P$1") (pintype "bidirectional"))
    )
    (net (code "102") (name "Net-(U1-ANT)") (class "Default")
      (node (ref "L4") (pin "1") (pinfunction "1_1") (pintype "passive"))
      (node (ref "U1") (pin "11") (pinfunction "ANT_11") (pintype "bidirectional"))
    )
    (net (code "103") (name "Net-(U1-BIAS)") (class "Default")
      (node (ref "R2") (pin "2") (pinfunction "2_2") (pintype "passive"))
      (node (ref "U1") (pin "15") (pinfunction "BIAS_15") (pintype "bidirectional"))
    )
    (net (code "104") (name "Net-(U1-HGM)") (class "Default")
      (node (ref "R1") (pin "1") (pinfunction "1_1") (pintype "passive"))
      (node (ref "U1") (pin "7") (pinfunction "HGM_7") (pintype "bidirectional"))
    )
    (net (code "105") (name "Net-(U2-AD0{slash}GIO7)") (class "Default")
      (node (ref "L11") (pin "2") (pinfunction "2_2") (pintype "passive"))
      (node (ref "U2") (pin "16") (pinfunction "AD0/GIO7_16") (pintype "bidirectional"))
    )
    (net (code "106") (name "Net-(U2-AD1{slash}GIO8)") (class "Default")
      (node (ref "L13") (pin "2") (pinfunction "2_2") (pintype "passive"))
      (node (ref "U2") (pin "17") (pinfunction "AD1/GIO8_17") (pintype "bidirectional"))
    )
    (net (code "107") (name "Net-(U2-BCLK{slash}GIO5)") (class "Default")
      (node (ref "L9") (pin "2") (pinfunction "2_2") (pintype "passive"))
      (node (ref "U2") (pin "14") (pinfunction "BCLK/GIO5_14") (pintype "bidirectional"))
    )
    (net (code "108") (name "Net-(U2-DCPL)") (class "Default")
      (node (ref "C25") (pin "1") (pinfunction "1_1") (pintype "passive"))
      (node (ref "U2") (pin "39") (pinfunction "DCPL_39") (pintype "bidirectional"))
    )
    (net (code "109") (name "Net-(U2-GIO3)") (class "Default")
      (node (ref "R4") (pin "1") (pinfunction "1_1") (pintype "passive"))
      (node (ref "U2") (pin "9") (pinfunction "GIO3_9") (pintype "bidirectional"))
    )
    (net (code "110") (name "Net-(U2-MCLK{slash}GIO4)") (class "Default")
      (node (ref "L8") (pin "2") (pinfunction "2_2") (pintype "passive"))
      (node (ref "U2") (pin "13") (pinfunction "MCLK/GIO4_13") (pintype "bidirectional"))
    )
    (net (code "111") (name "Net-(U2-RBIAS)") (class "Default")
      (node (ref "R3") (pin "2") (pinfunction "2_2") (pintype "passive"))
      (node (ref "U2") (pin "30") (pinfunction "RBIAS_30") (pintype "bidirectional"))
    )
    (net (code "112") (name "Net-(U2-WCLK{slash}GIO6)") (class "Default")
      (node (ref "L10") (pin "2") (pinfunction "2_2") (pintype "passive"))
      (node (ref "U2") (pin "15") (pinfunction "WCLK/GIO6_15") (pintype "bidirectional"))
    )
    (net (code "113") (name "Net-(U2-X0)") (class "Default")
      (node (ref "C27") (pin "1") (pinfunction "1_1") (pintype "passive"))
      (node (ref "U2") (pin "22") (pinfunction "X0_22") (pintype "bidirectional"))
      (node (ref "X1") (pin "3") (pinfunction "2_3") (pintype "passive"))
    )
    (net (code "114") (name "Net-(U2-X1)") (class "Default")
      (node (ref "C26") (pin "1") (pinfunction "1_1") (pintype "passive"))
      (node (ref "U2") (pin "21") (pinfunction "X1_21") (pintype "bidirectional"))
      (node (ref "X1") (pin "1") (pinfunction "1_1") (pintype "passive"))
    )
    (net (code "115") (name "Net-(U2-XPAEN)") (class "Default")
      (node (ref "L12") (pin "1") (pinfunction "1_1") (pintype "passive"))
      (node (ref "U2") (pin "36") (pinfunction "XPAEN_36") (pintype "bidirectional"))
    )
    (net (code "116") (name "Net-(U2-~{RESET})") (class "Default")
      (node (ref "L7") (pin "1") (pinfunction "1_1") (pintype "passive"))
      (node (ref "U2") (pin "11") (pinfunction "~{RESET}_11") (pintype "bidirectional"))
    )
    (net (code "117") (name "Net-(U3-AINA)") (class "Default")
      (node (ref "C36") (pin "2") (pinfunction "2_2") (pintype "passive"))
      (node (ref "U3") (pin "15") (pinfunction "AINA_15") (pintype "bidirectional"))
    )
    (net (code "118") (name "Net-(U3-AINB)") (class "Default")
      (node (ref "C38") (pin "2") (pinfunction "2_2") (pintype "passive"))
      (node (ref "U3") (pin "16") (pinfunction "AINB_16") (pintype "bidirectional"))
    )
    (net (code "119") (name "Net-(U3-FILT+)") (class "Default")
      (node (ref "C44") (pin "1") (pinfunction "1_1") (pintype "passive"))
      (node (ref "C45") (pin "1") (pinfunction "1_1") (pintype "passive"))
      (node (ref "U3") (pin "18") (pinfunction "FILT+_18") (pintype "bidirectional"))
    )
    (net (code "120") (name "Net-(U3-VQ)") (class "Default")
      (node (ref "C46") (pin "1") (pinfunction "1_1") (pintype "passive"))
      (node (ref "C47") (pin "1") (pinfunction "1_1") (pintype "passive"))
      (node (ref "U3") (pin "17") (pinfunction "VQ_17") (pintype "bidirectional"))
    )
    (net (code "121") (name "Net-(U4-BYPASS)") (class "Default")
      (node (ref "C63") (pin "1") (pinfunction "1_1") (pintype "passive"))
      (node (ref "U4") (pin "1") (pinfunction "BYPASS_1") (pintype "bidirectional"))
    )
    (net (code "122") (name "Net-(U4-INA)") (class "Default")
      (node (ref "R7") (pin "2") (pinfunction "2_2") (pintype "passive"))
      (node (ref "R9") (pin "1") (pinfunction "1_1") (pintype "passive"))
      (node (ref "U4") (pin "8") (pinfunction "INA_8") (pintype "bidirectional"))
    )
    (net (code "123") (name "Net-(U4-INB)") (class "Default")
      (node (ref "R14") (pin "1") (pinfunction "1_1") (pintype "passive"))
      (node (ref "R21") (pin "2") (pinfunction "2_2") (pintype "passive"))
      (node (ref "U4") (pin "4") (pinfunction "INB_4") (pintype "bidirectional"))
    )
    (net (code "124") (name "Net-(U4-OUTB)") (class "Default")
      (node (ref "C66") (pin "1") (pinfunction "1_1") (pintype "passive"))
      (node (ref "R21") (pin "1") (pinfunction "1_1") (pintype "passive"))
      (node (ref "U4") (pin "5") (pinfunction "OUTB_5") (pintype "bidirectional"))
    )
    (net (code "125") (name "Net-(U4-SHUTDOWN)") (class "Default")
      (node (ref "R10") (pin "1") (pinfunction "1_1") (pintype "passive"))
      (node (ref "U4") (pin "3") (pinfunction "SHUTDOWN_3") (pintype "bidirectional"))
    )
    (net (code "126") (name "Net-(U5-VIN)") (class "Default")
      (node (ref "F1") (pin "2") (pinfunction "2_2") (pintype "passive"))
      (node (ref "L21") (pin "2") (pinfunction "2_2") (pintype "passive"))
      (node (ref "U5") (pin "1") (pinfunction "VIN_1") (pintype "bidirectional"))
    )
    (net (code "127") (name "Net-(U6-ISET)") (class "Default")
      (node (ref "R38") (pin "2") (pinfunction "2_2") (pintype "passive"))
      (node (ref "U6") (pin "2") (pinfunction "ISET_2") (pintype "bidirectional"))
    )
    (net (code "128") (name "Net-(U6-PRETERM)") (class "Default")
      (node (ref "R39") (pin "2") (pinfunction "2_2") (pintype "passive"))
      (node (ref "U6") (pin "4") (pinfunction "PRETERM_4") (pintype "bidirectional"))
    )
    (net (code "129") (name "Net-(U6-TS)") (class "Default")
      (node (ref "R37") (pin "2") (pinfunction "2_2") (pintype "passive"))
      (node (ref "U6") (pin "9") (pinfunction "TS_9") (pintype "bidirectional"))
    )
    (net (code "130") (name "Net-(U6-~{CHG})") (class "Default")
      (node (ref "CHARGE") (pin "C") (pinfunction "C_C") (pintype "passive"))
      (node (ref "U6") (pin "8") (pinfunction "~{CHG}_8") (pintype "bidirectional"))
    )
    (net (code "131") (name "Net-(U7-EN)") (class "Default")
      (node (ref "C71") (pin "1") (pinfunction "1_1") (pintype "passive"))
      (node (ref "L21") (pin "1") (pinfunction "1_1") (pintype "passive"))
      (node (ref "U7") (pin "1") (pinfunction "VIN_1") (pintype "bidirectional"))
      (node (ref "U7") (pin "3") (pinfunction "EN_3") (pintype "bidirectional"))
    )
    (net (code "132") (name "Net-(U9-FILTP)") (class "Default")
      (node (ref "C82") (pin "1") (pinfunction "1_1") (pintype "passive"))
      (node (ref "U9") (pin "6") (pinfunction "FILTP_6") (pintype "bidirectional"))
    )
    (net (code "133") (name "Net-(U10C-PC02)") (class "Default")
      (node (ref "C83") (pin "1") (pinfunction "1_1") (pintype "passive"))
      (node (ref "U10") (pin "18") (pinfunction "PC02_18") (pintype "bidirectional"))
      (node (ref "X2") (pin "X1") (pinfunction "1_X1") (pintype "passive"))
    )
    (net (code "134") (name "Net-(U10C-PC03)") (class "Default")
      (node (ref "C84") (pin "1") (pinfunction "1_1") (pintype "passive"))
      (node (ref "U10") (pin "19") (pinfunction "PC03_19") (pintype "bidirectional"))
      (node (ref "X2") (pin "X2") (pinfunction "2_X2") (pintype "passive"))
    )
    (net (code "135") (name "Net-(U10D-D+_FS)") (class "Default")
      (node (ref "R15") (pin "1") (pinfunction "1_1") (pintype "passive"))
      (node (ref "U10") (pin "9") (pinfunction "D+_FS_9") (pintype "bidirectional"))
    )
    (net (code "136") (name "Net-(U10D-D-_FS)") (class "Default")
      (node (ref "R17") (pin "1") (pinfunction "1_1") (pintype "passive"))
      (node (ref "U10") (pin "8") (pinfunction "D-_FS_8") (pintype "bidirectional"))
    )
    (net (code "137") (name "Net-(U10D-USB_VBIAS)") (class "Default")
      (node (ref "C76") (pin "1") (pinfunction "1_1") (pintype "passive"))
      (node (ref "R27") (pin "2") (pinfunction "2_2") (pintype "passive"))
      (node (ref "U10") (pin "3") (pinfunction "USB_VBIAS_3") (pintype "bidirectional"))
    )
    (net (code "138") (name "Net-(U10E-VDDCORE)") (class "Default")
      (node (ref "C68") (pin "1") (pinfunction "1_1") (pintype "passive"))
      (node (ref "C69") (pin "1") (pinfunction "1_1") (pintype "passive"))
      (node (ref "U10") (pin "141") (pinfunction "VDDCORE_141") (pintype "bidirectional"))
    )
    (net (code "139") (name "Net-(U10F-PX37)") (class "Default")
      (node (ref "U10") (pin "45") (pinfunction "PX37_45") (pintype "bidirectional"))
      (node (ref "U9") (pin "5") (pinfunction "CLK_IN_5") (pintype "bidirectional"))
    )
    (net (code "140") (name "Net-(U11-SNS0)") (class "Default")
      (node (ref "C87") (pin "1") (pinfunction "1_1") (pintype "passive"))
      (node (ref "U11") (pin "32") (pinfunction "SNS0_32") (pintype "bidirectional"))
    )
    (net (code "141") (name "Net-(U11-SNS0K)") (class "Default")
      (node (ref "C87") (pin "2") (pinfunction "2_2") (pintype "passive"))
      (node (ref "R29") (pin "1") (pinfunction "1_1") (pintype "passive"))
      (node (ref "U11") (pin "1") (pinfunction "SNS0K_1") (pintype "bidirectional"))
    )
    (net (code "142") (name "Net-(U11-SNS1)") (class "Default")
      (node (ref "C88") (pin "1") (pinfunction "1_1") (pintype "passive"))
      (node (ref "U11") (pin "2") (pinfunction "SNS1_2") (pintype "bidirectional"))
    )
    (net (code "143") (name "Net-(U11-SNS1K)") (class "Default")
      (node (ref "C88") (pin "2") (pinfunction "2_2") (pintype "passive"))
      (node (ref "R30") (pin "1") (pinfunction "1_1") (pintype "passive"))
      (node (ref "U11") (pin "3") (pinfunction "SNS1K_3") (pintype "bidirectional"))
    )
    (net (code "144") (name "Net-(U11-SNS2)") (class "Default")
      (node (ref "C89") (pin "1") (pinfunction "1_1") (pintype "passive"))
      (node (ref "U11") (pin "7") (pinfunction "SNS2_7") (pintype "bidirectional"))
    )
    (net (code "145") (name "Net-(U11-SNS2K)") (class "Default")
      (node (ref "C89") (pin "2") (pinfunction "2_2") (pintype "passive"))
      (node (ref "R31") (pin "1") (pinfunction "1_1") (pintype "passive"))
      (node (ref "U11") (pin "6") (pinfunction "SNS2K_6") (pintype "bidirectional"))
    )
    (net (code "146") (name "Net-(U11-SNS3)") (class "Default")
      (node (ref "C90") (pin "1") (pinfunction "1_1") (pintype "passive"))
      (node (ref "U11") (pin "8") (pinfunction "SNS3_8") (pintype "bidirectional"))
    )
    (net (code "147") (name "Net-(U11-SNS3K)") (class "Default")
      (node (ref "C90") (pin "2") (pinfunction "2_2") (pintype "passive"))
      (node (ref "R32") (pin "1") (pinfunction "1_1") (pintype "passive"))
      (node (ref "U11") (pin "9") (pinfunction "SNS3K_9") (pintype "bidirectional"))
    )
    (net (code "148") (name "Net-(U11-SNS4)") (class "Default")
      (node (ref "C91") (pin "1") (pinfunction "1_1") (pintype "passive"))
      (node (ref "U11") (pin "10") (pinfunction "SNS4_10") (pintype "bidirectional"))
    )
    (net (code "149") (name "Net-(U11-SNS4K)") (class "Default")
      (node (ref "C91") (pin "2") (pinfunction "2_2") (pintype "passive"))
      (node (ref "R33") (pin "1") (pinfunction "1_1") (pintype "passive"))
      (node (ref "U11") (pin "11") (pinfunction "SNS4K_11") (pintype "bidirectional"))
    )
    (net (code "150") (name "Net-(U11-SNS5)") (class "Default")
      (node (ref "C92") (pin "1") (pinfunction "1_1") (pintype "passive"))
      (node (ref "U11") (pin "12") (pinfunction "SNS5_12") (pintype "bidirectional"))
    )
    (net (code "151") (name "Net-(U11-SNS5K)") (class "Default")
      (node (ref "C92") (pin "2") (pinfunction "2_2") (pintype "passive"))
      (node (ref "R34") (pin "1") (pinfunction "1_1") (pintype "passive"))
      (node (ref "U11") (pin "13") (pinfunction "SNS5K_13") (pintype "bidirectional"))
    )
    (net (code "152") (name "Net-(U11-SNS6)") (class "Default")
      (node (ref "C93") (pin "1") (pinfunction "1_1") (pintype "passive"))
      (node (ref "U11") (pin "20") (pinfunction "SNS6_20") (pintype "bidirectional"))
    )
    (net (code "153") (name "Net-(U11-SNS6K)") (class "Default")
      (node (ref "C93") (pin "2") (pinfunction "2_2") (pintype "passive"))
      (node (ref "R35") (pin "1") (pinfunction "1_1") (pintype "passive"))
      (node (ref "U11") (pin "19") (pinfunction "SNS6K_19") (pintype "bidirectional"))
    )
    (net (code "154") (name "Net-(U11-SNS7K{slash}DETECT0)") (class "Default")
      (node (ref "C94") (pin "2") (pinfunction "2_2") (pintype "passive"))
      (node (ref "R36") (pin "1") (pinfunction "1_1") (pintype "passive"))
      (node (ref "U11") (pin "22") (pinfunction "SNS7K/DETECT0_22") (pintype "bidirectional"))
    )
    (net (code "155") (name "Net-(U11-SNS7{slash}DETECT1)") (class "Default")
      (node (ref "C94") (pin "1") (pinfunction "1_1") (pintype "passive"))
      (node (ref "U11") (pin "23") (pinfunction "SNS7/DETECT1_23") (pintype "bidirectional"))
    )
    (net (code "156") (name "Net-(U11-~{RESET})") (class "Default")
      (node (ref "R28") (pin "1") (pinfunction "1_1") (pintype "passive"))
      (node (ref "U11") (pin "29") (pinfunction "~{RESET}_29") (pintype "bidirectional"))
    )
    (net (code "157") (name "OUT_L") (class "Default")
      (node (ref "R41") (pin "2") (pinfunction "2_2") (pintype "passive"))
      (node (ref "U3") (pin "23") (pinfunction "OUTB_23") (pintype "bidirectional"))
    )
    (net (code "158") (name "OUT_R") (class "Default")
      (node (ref "R40") (pin "2") (pinfunction "2_2") (pintype "passive"))
      (node (ref "U3") (pin "22") (pinfunction "OUTA_22") (pintype "bidirectional"))
    )
    (net (code "159") (name "PA_EN") (class "Default")
      (node (ref "L12") (pin "2") (pinfunction "2_2") (pintype "passive"))
      (node (ref "R6") (pin "2") (pinfunction "2_2") (pintype "passive"))
      (node (ref "U1") (pin "5") (pinfunction "PAEN_5") (pintype "bidirectional"))
    )
    (net (code "160") (name "PHONE_L") (class "Default")
      (node (ref "C53") (pin "2") (pinfunction "2_2") (pintype "passive"))
      (node (ref "PHONE_OUT") (pin "4") (pinfunction "L_4") (pintype "bidirectional"))
      (node (ref "R25") (pin "2") (pinfunction "2_2") (pintype "passive"))
    )
    (net (code "161") (name "PHONE_R") (class "Default")
      (node (ref "C66") (pin "2") (pinfunction "2_2") (pintype "passive"))
      (node (ref "PHONE_OUT") (pin "1") (pinfunction "R_1") (pintype "bidirectional"))
    )
    (net (code "162") (name "PHONE_SENSE") (class "Default")
      (node (ref "PHONE_OUT") (pin "3") (pinfunction "L_SW_3") (pintype "bidirectional"))
      (node (ref "R16") (pin "1") (pinfunction "1_1") (pintype "passive"))
      (node (ref "U10") (pin "115") (pinfunction "PA18_115") (pintype "bidirectional"))
    )
    (net (code "163") (name "RED_BOT") (class "Default")
      (node (ref "TO_AUX1") (pin "4") (pinfunction "4_4") (pintype "bidirectional"))
      (node (ref "U10") (pin "132") (pinfunction "PA12_132") (pintype "bidirectional"))
    )
    (net (code "164") (name "RED_TOP") (class "Default")
      (node (ref "TO_AUX1") (pin "7") (pinfunction "7_7") (pintype "bidirectional"))
      (node (ref "U10") (pin "83") (pinfunction "PX17_83") (pintype "bidirectional"))
    )
    (net (code "165") (name "RF_N") (class "Default")
      (node (ref "U1") (pin "2") (pinfunction "RF_N_2") (pintype "bidirectional"))
      (node (ref "U2") (pin "25") (pinfunction "RF_N_25") (pintype "bidirectional"))
    )
    (net (code "166") (name "RF_P") (class "Default")
      (node (ref "U1") (pin "4") (pinfunction "RF_P_4") (pintype "bidirectional"))
      (node (ref "U2") (pin "24") (pinfunction "RF_P_24") (pintype "bidirectional"))
    )
    (net (code "167") (name "RTS") (class "Default")
      (node (ref "SERIAL") (pin "1") (pinfunction "1_1") (pintype "bidirectional"))
      (node (ref "U10") (pin "63") (pinfunction "PX03_63") (pintype "bidirectional"))
    )
    (net (code "168") (name "RXD") (class "Default")
      (node (ref "SERIAL") (pin "3") (pinfunction "3_3") (pintype "bidirectional"))
      (node (ref "U10") (pin "55") (pinfunction "PX00_55") (pintype "bidirectional"))
    )
    (net (code "169") (name "SCLK0") (class "Default")
      (node (ref "CC_DEBUG") (pin "6") (pinfunction "6_6") (pintype "bidirectional"))
      (node (ref "U10") (pin "137") (pinfunction "PA08_137") (pintype "bidirectional"))
      (node (ref "U2") (pin "4") (pinfunction "SCLK_4") (pintype "bidirectional"))
      (node (ref "U3") (pin "10") (pinfunction "SCL/SCLK_10") (pintype "bidirectional"))
      (node (ref "U9") (pin "9") (pinfunction "SCL/SCLK_9") (pintype "bidirectional"))
    )
    (net (code "170") (name "SCLK1") (class "Default")
      (node (ref "TO_AUX2") (pin "1") (pinfunction "1_1") (pintype "bidirectional"))
      (node (ref "U10") (pin "135") (pinfunction "PB07_135") (pintype "bidirectional"))
    )
    (net (code "171") (name "TCK") (class "Default")
      (node (ref "JTAG") (pin "1") (pinfunction "1_1") (pintype "bidirectional"))
      (node (ref "U10") (pin "107") (pinfunction "TCK_107") (pintype "bidirectional"))
    )
    (net (code "172") (name "TDI") (class "Default")
      (node (ref "JTAG") (pin "9") (pinfunction "9_9") (pintype "bidirectional"))
      (node (ref "U10") (pin "108") (pinfunction "TDI_108") (pintype "bidirectional"))
    )
    (net (code "173") (name "TDO") (class "Default")
      (node (ref "JTAG") (pin "3") (pinfunction "3_3") (pintype "bidirectional"))
      (node (ref "U10") (pin "105") (pinfunction "TDO_105") (pintype "bidirectional"))
    )
    (net (code "174") (name "TMS") (class "Default")
      (node (ref "JTAG") (pin "5") (pinfunction "5_5") (pintype "bidirectional"))
      (node (ref "U10") (pin "104") (pinfunction "TMS_104") (pintype "bidirectional"))
    )
    (net (code "175") (name "TXD") (class "Default")
      (node (ref "SERIAL") (pin "2") (pinfunction "2_2") (pintype "bidirectional"))
      (node (ref "U10") (pin "59") (pinfunction "PX01_59") (pintype "bidirectional"))
    )
    (net (code "176") (name "UC_MCLK") (class "Default")
      (node (ref "U10") (pin "13") (pinfunction "PC04_13") (pintype "bidirectional"))
      (node (ref "U8") (pin "1") (pinfunction "D_1") (pintype "bidirectional"))
      (node (ref "U8") (pin "4") (pinfunction "~{Q}_4") (pintype "bidirectional"))
    )
    (net (code "177") (name "USBOTGID") (class "Default")
      (node (ref "U10") (pin "121") (pinfunction "PB05_121") (pintype "bidirectional"))
      (node (ref "USB") (pin "4") (pinfunction "ID_4") (pintype "bidirectional"))
    )
    (net (code "178") (name "WCLK") (class "Default")
      (node (ref "L10") (pin "1") (pinfunction "1_1") (pintype "passive"))
      (node (ref "U10") (pin "44") (pinfunction "PX36_44") (pintype "bidirectional"))
      (node (ref "U10") (pin "89") (pinfunction "PX27_89") (pintype "bidirectional"))
      (node (ref "U10") (pin "90") (pinfunction "PX26_90") (pintype "bidirectional"))
      (node (ref "U3") (pin "2") (pinfunction "WCLK_2") (pintype "bidirectional"))
    )
    (net (code "179") (name "unconnected-(CC_DEBUG-Pad3)") (class "Default")
      (node (ref "CC_DEBUG") (pin "3") (pinfunction "3_3") (pintype "bidirectional"))
    )
    (net (code "180") (name "unconnected-(CC_DEBUG-Pad4)") (class "Default")
      (node (ref "CC_DEBUG") (pin "4") (pinfunction "4_4") (pintype "bidirectional"))
    )
    (net (code "181") (name "unconnected-(CC_DEBUG-Pad9)") (class "Default")
      (node (ref "CC_DEBUG") (pin "9") (pinfunction "9_9") (pintype "bidirectional"))
    )
    (net (code "182") (name "unconnected-(GPIO-Pad1)") (class "Default")
      (node (ref "GPIO") (pin "1") (pinfunction "1_1") (pintype "bidirectional"))
    )
    (net (code "183") (name "unconnected-(GPIO-Pad3)") (class "Default")
      (node (ref "GPIO") (pin "3") (pinfunction "3_3") (pintype "bidirectional"))
    )
    (net (code "184") (name "unconnected-(JTAG-Pad7)") (class "Default")
      (node (ref "JTAG") (pin "7") (pinfunction "7_7") (pintype "bidirectional"))
    )
    (net (code "185") (name "unconnected-(JTAG-Pad8)") (class "Default")
      (node (ref "JTAG") (pin "8") (pinfunction "8_8") (pintype "bidirectional"))
    )
    (net (code "186") (name "unconnected-(LINE_IN-R_SW-Pad2)") (class "Default")
      (node (ref "LINE_IN") (pin "2") (pinfunction "R_SW_2") (pintype "bidirectional"))
    )
    (net (code "187") (name "unconnected-(PHONE_OUT-R_SW-Pad2)") (class "Default")
      (node (ref "PHONE_OUT") (pin "2") (pinfunction "R_SW_2") (pintype "bidirectional"))
    )
    (net (code "188") (name "unconnected-(RESET-Pad2)") (class "Default")
      (node (ref "RESET") (pin "2") (pinfunction "2_2") (pintype "bidirectional"))
    )
    (net (code "189") (name "unconnected-(RESET-Pad4)") (class "Default")
      (node (ref "RESET") (pin "4") (pinfunction "4_4") (pintype "bidirectional"))
    )
    (net (code "190") (name "unconnected-(SERIAL-Pad4)") (class "Default")
      (node (ref "SERIAL") (pin "4") (pinfunction "4_4") (pintype "bidirectional"))
    )
    (net (code "191") (name "unconnected-(U1-RXTX-Pad3)") (class "Default")
      (node (ref "U1") (pin "3") (pinfunction "RXTX_3") (pintype "bidirectional"))
    )
    (net (code "192") (name "unconnected-(U2-GIO2-Pad8)") (class "Default")
      (node (ref "U2") (pin "8") (pinfunction "GIO2_8") (pintype "bidirectional"))
    )
    (net (code "193") (name "unconnected-(U2-USBN{slash}XANTN-Pad1)") (class "Default")
      (node (ref "U2") (pin "1") (pinfunction "USBN/XANTN_1") (pintype "bidirectional"))
    )
    (net (code "194") (name "unconnected-(U2-USBP{slash}XANTP-Pad2)") (class "Default")
      (node (ref "U2") (pin "2") (pinfunction "USBP/XANTP_2") (pintype "bidirectional"))
    )
    (net (code "195") (name "unconnected-(U3-AD2-Pad13)") (class "Default")
      (node (ref "U3") (pin "13") (pinfunction "AD2_13") (pintype "bidirectional"))
    )
    (net (code "196") (name "unconnected-(U6-~{PG}-Pad5)") (class "Default")
      (node (ref "U6") (pin "5") (pinfunction "~{PG}_5") (pintype "bidirectional"))
    )
    (net (code "197") (name "unconnected-(U9-AUX_OUT-Pad4)") (class "Default")
      (node (ref "U9") (pin "4") (pinfunction "AUX_OUT_4") (pintype "bidirectional"))
    )
    (net (code "198") (name "unconnected-(U10A-PA00-Pad122)") (class "Default")
      (node (ref "U10") (pin "122") (pinfunction "PA00_122") (pintype "bidirectional"))
    )
    (net (code "199") (name "unconnected-(U10A-PA01-Pad123)") (class "Default")
      (node (ref "U10") (pin "123") (pinfunction "PA01_123") (pintype "bidirectional"))
    )
    (net (code "200") (name "unconnected-(U10A-PA02-Pad15)") (class "Default")
      (node (ref "U10") (pin "15") (pinfunction "PA02_15") (pintype "bidirectional"))
    )
    (net (code "201") (name "unconnected-(U10A-PA05-Pad124)") (class "Default")
      (node (ref "U10") (pin "124") (pinfunction "PA05_124") (pintype "bidirectional"))
    )
    (net (code "202") (name "unconnected-(U10A-PA15-Pad101)") (class "Default")
      (node (ref "U10") (pin "101") (pinfunction "PA15_101") (pintype "bidirectional"))
    )
    (net (code "203") (name "unconnected-(U10A-PA16-Pad128)") (class "Default")
      (node (ref "U10") (pin "128") (pinfunction "PA16_128") (pintype "bidirectional"))
    )
    (net (code "204") (name "unconnected-(U10A-PA20-Pad113)") (class "Default")
      (node (ref "U10") (pin "113") (pinfunction "PA20_113") (pintype "bidirectional"))
    )
    (net (code "205") (name "unconnected-(U10A-PA21-Pad109)") (class "Default")
      (node (ref "U10") (pin "109") (pinfunction "PA21_109") (pintype "bidirectional"))
    )
    (net (code "206") (name "unconnected-(U10A-PA22-Pad110)") (class "Default")
      (node (ref "U10") (pin "110") (pinfunction "PA22_110") (pintype "bidirectional"))
    )
    (net (code "207") (name "unconnected-(U10A-PA25-Pad119)") (class "Default")
      (node (ref "U10") (pin "119") (pinfunction "PA25_119") (pintype "bidirectional"))
    )
    (net (code "208") (name "unconnected-(U10A-PA26-Pad120)") (class "Default")
      (node (ref "U10") (pin "120") (pinfunction "PA26_120") (pintype "bidirectional"))
    )
    (net (code "209") (name "unconnected-(U10B-PB02-Pad25)") (class "Default")
      (node (ref "U10") (pin "25") (pinfunction "PB02_25") (pintype "bidirectional"))
    )
    (net (code "210") (name "unconnected-(U10B-PB03-Pad24)") (class "Default")
      (node (ref "U10") (pin "24") (pinfunction "PB03_24") (pintype "bidirectional"))
    )
    (net (code "211") (name "unconnected-(U10B-PB04-Pad22)") (class "Default")
      (node (ref "U10") (pin "22") (pinfunction "PB04_22") (pintype "bidirectional"))
    )
    (net (code "212") (name "unconnected-(U10B-PB06-Pad134)") (class "Default")
      (node (ref "U10") (pin "134") (pinfunction "PB06_134") (pintype "bidirectional"))
    )
    (net (code "213") (name "unconnected-(U10B-PB09-Pad17)") (class "Default")
      (node (ref "U10") (pin "17") (pinfunction "PB09_17") (pintype "bidirectional"))
    )
    (net (code "214") (name "unconnected-(U10B-PB11-Pad31)") (class "Default")
      (node (ref "U10") (pin "31") (pinfunction "PB11_31") (pintype "bidirectional"))
    )
    (net (code "215") (name "unconnected-(U10C-PC00-Pad98)") (class "Default")
      (node (ref "U10") (pin "98") (pinfunction "PC00_98") (pintype "bidirectional"))
    )
    (net (code "216") (name "unconnected-(U10C-PC01-Pad99)") (class "Default")
      (node (ref "U10") (pin "99") (pinfunction "PC01_99") (pintype "bidirectional"))
    )
    (net (code "217") (name "unconnected-(U10C-PC05-Pad12)") (class "Default")
      (node (ref "U10") (pin "12") (pinfunction "PC05_12") (pintype "bidirectional"))
    )
    (net (code "218") (name "unconnected-(U10F-PX04-Pad60)") (class "Default")
      (node (ref "U10") (pin "60") (pinfunction "PX04_60") (pintype "bidirectional"))
    )
    (net (code "219") (name "unconnected-(U10F-PX05-Pad58)") (class "Default")
      (node (ref "U10") (pin "58") (pinfunction "PX05_58") (pintype "bidirectional"))
    )
    (net (code "220") (name "unconnected-(U10F-PX06-Pad53)") (class "Default")
      (node (ref "U10") (pin "53") (pinfunction "PX06_53") (pintype "bidirectional"))
    )
    (net (code "221") (name "unconnected-(U10F-PX07-Pad54)") (class "Default")
      (node (ref "U10") (pin "54") (pinfunction "PX07_54") (pintype "bidirectional"))
    )
    (net (code "222") (name "unconnected-(U10F-PX09-Pad49)") (class "Default")
      (node (ref "U10") (pin "49") (pinfunction "PX09_49") (pintype "bidirectional"))
    )
    (net (code "223") (name "unconnected-(U10F-PX10-Pad37)") (class "Default")
      (node (ref "U10") (pin "37") (pinfunction "PX10_37") (pintype "bidirectional"))
    )
    (net (code "224") (name "unconnected-(U10F-PX11-Pad67)") (class "Default")
      (node (ref "U10") (pin "67") (pinfunction "PX11_67") (pintype "bidirectional"))
    )
    (net (code "225") (name "unconnected-(U10F-PX13-Pad33)") (class "Default")
      (node (ref "U10") (pin "33") (pinfunction "PX13_33") (pintype "bidirectional"))
    )
    (net (code "226") (name "unconnected-(U10F-PX16-Pad32)") (class "Default")
      (node (ref "U10") (pin "32") (pinfunction "PX16_32") (pintype "bidirectional"))
    )
    (net (code "227") (name "unconnected-(U10F-PX19-Pad35)") (class "Default")
      (node (ref "U10") (pin "35") (pinfunction "PX19_35") (pintype "bidirectional"))
    )
    (net (code "228") (name "unconnected-(U10F-PX20-Pad73)") (class "Default")
      (node (ref "U10") (pin "73") (pinfunction "PX20_73") (pintype "bidirectional"))
    )
    (net (code "229") (name "unconnected-(U10F-PX21-Pad80)") (class "Default")
      (node (ref "U10") (pin "80") (pinfunction "PX21_80") (pintype "bidirectional"))
    )
    (net (code "230") (name "unconnected-(U10F-PX22-Pad72)") (class "Default")
      (node (ref "U10") (pin "72") (pinfunction "PX22_72") (pintype "bidirectional"))
    )
    (net (code "231") (name "unconnected-(U10F-PX29-Pad94)") (class "Default")
      (node (ref "U10") (pin "94") (pinfunction "PX29_94") (pintype "bidirectional"))
    )
    (net (code "232") (name "unconnected-(U10F-PX39-Pad52)") (class "Default")
      (node (ref "U10") (pin "52") (pinfunction "PX39_52") (pintype "bidirectional"))
    )
    (net (code "233") (name "unconnected-(U10F-PX40-Pad36)") (class "Default")
      (node (ref "U10") (pin "36") (pinfunction "PX40_36") (pintype "bidirectional"))
    )
    (net (code "234") (name "unconnected-(U10F-PX41-Pad71)") (class "Default")
      (node (ref "U10") (pin "71") (pinfunction "PX41_71") (pintype "bidirectional"))
    )
    (net (code "235") (name "unconnected-(U10F-PX42-Pad69)") (class "Default")
      (node (ref "U10") (pin "69") (pinfunction "PX42_69") (pintype "bidirectional"))
    )
    (net (code "236") (name "unconnected-(U10F-PX43-Pad88)") (class "Default")
      (node (ref "U10") (pin "88") (pinfunction "PX43_88") (pintype "bidirectional"))
    )
    (net (code "237") (name "unconnected-(U10F-PX44-Pad66)") (class "Default")
      (node (ref "U10") (pin "66") (pinfunction "PX44_66") (pintype "bidirectional"))
    )
    (net (code "238") (name "unconnected-(U10F-PX45-Pad70)") (class "Default")
      (node (ref "U10") (pin "70") (pinfunction "PX45_70") (pintype "bidirectional"))
    )
    (net (code "239") (name "unconnected-(U10F-PX47-Pad39)") (class "Default")
      (node (ref "U10") (pin "39") (pinfunction "PX47_39") (pintype "bidirectional"))
    )
    (net (code "240") (name "unconnected-(U10F-PX48-Pad41)") (class "Default")
      (node (ref "U10") (pin "41") (pinfunction "PX48_41") (pintype "bidirectional"))
    )
    (net (code "241") (name "unconnected-(U10F-PX49-Pad43)") (class "Default")
      (node (ref "U10") (pin "43") (pinfunction "PX49_43") (pintype "bidirectional"))
    )
    (net (code "242") (name "unconnected-(U10F-PX51-Pad77)") (class "Default")
      (node (ref "U10") (pin "77") (pinfunction "PX51_77") (pintype "bidirectional"))
    )
    (net (code "243") (name "unconnected-(U10F-PX52-Pad87)") (class "Default")
      (node (ref "U10") (pin "87") (pinfunction "PX52_87") (pintype "bidirectional"))
    )
    (net (code "244") (name "unconnected-(U10F-PX53-Pad42)") (class "Default")
      (node (ref "U10") (pin "42") (pinfunction "PX53_42") (pintype "bidirectional"))
    )
    (net (code "245") (name "unconnected-(U10F-PX54-Pad46)") (class "Default")
      (node (ref "U10") (pin "46") (pinfunction "PX54_46") (pintype "bidirectional"))
    )
    (net (code "246") (name "unconnected-(U10F-PX55-Pad79)") (class "Default")
      (node (ref "U10") (pin "79") (pinfunction "PX55_79") (pintype "bidirectional"))
    )
    (net (code "247") (name "unconnected-(U10F-PX56-Pad78)") (class "Default")
      (node (ref "U10") (pin "78") (pinfunction "PX56_78") (pintype "bidirectional"))
    )
    (net (code "248") (name "unconnected-(U10F-PX57-Pad76)") (class "Default")
      (node (ref "U10") (pin "76") (pinfunction "PX57_76") (pintype "bidirectional"))
    )
    (net (code "249") (name "unconnected-(U10F-PX58-Pad57)") (class "Default")
      (node (ref "U10") (pin "57") (pinfunction "PX58_57") (pintype "bidirectional"))
    )
    (net (code "250") (name "unconnected-(U10F-PX59-Pad56)") (class "Default")
      (node (ref "U10") (pin "56") (pinfunction "PX59_56") (pintype "bidirectional"))
    )
    (net (code "251") (name "unconnected-(U11-SNS8K{slash}DETECT3-Pad25)") (class "Default")
      (node (ref "U11") (pin "25") (pinfunction "SNS8K/DETECT3_25") (pintype "bidirectional"))
    )
    (net (code "252") (name "unconnected-(U11-SNS8{slash}DETECT2-Pad24)") (class "Default")
      (node (ref "U11") (pin "24") (pinfunction "SNS8/DETECT2_24") (pintype "bidirectional"))
    )
    (net (code "253") (name "unconnected-(U11-SNS9K{slash}DETECT5-Pad27)") (class "Default")
      (node (ref "U11") (pin "27") (pinfunction "SNS9K/DETECT5_27") (pintype "bidirectional"))
    )
    (net (code "254") (name "unconnected-(U11-SNS9{slash}DETECT4-Pad26)") (class "Default")
      (node (ref "U11") (pin "26") (pinfunction "SNS9/DETECT4_26") (pintype "bidirectional"))
    )
    (net (code "255") (name "unconnected-(U11-SNS10K{slash}SYNC-Pad31)") (class "Default")
      (node (ref "U11") (pin "31") (pinfunction "SNS10K/SYNC_31") (pintype "bidirectional"))
    )
    (net (code "256") (name "unconnected-(U11-SNS10{slash}DETECT16-Pad30)") (class "Default")
      (node (ref "U11") (pin "30") (pinfunction "SNS10/DETECT16_30") (pintype "bidirectional"))
    )
  )
)
